# Conectores.net
KiCad netlist of a schematic drawn in EAGLE
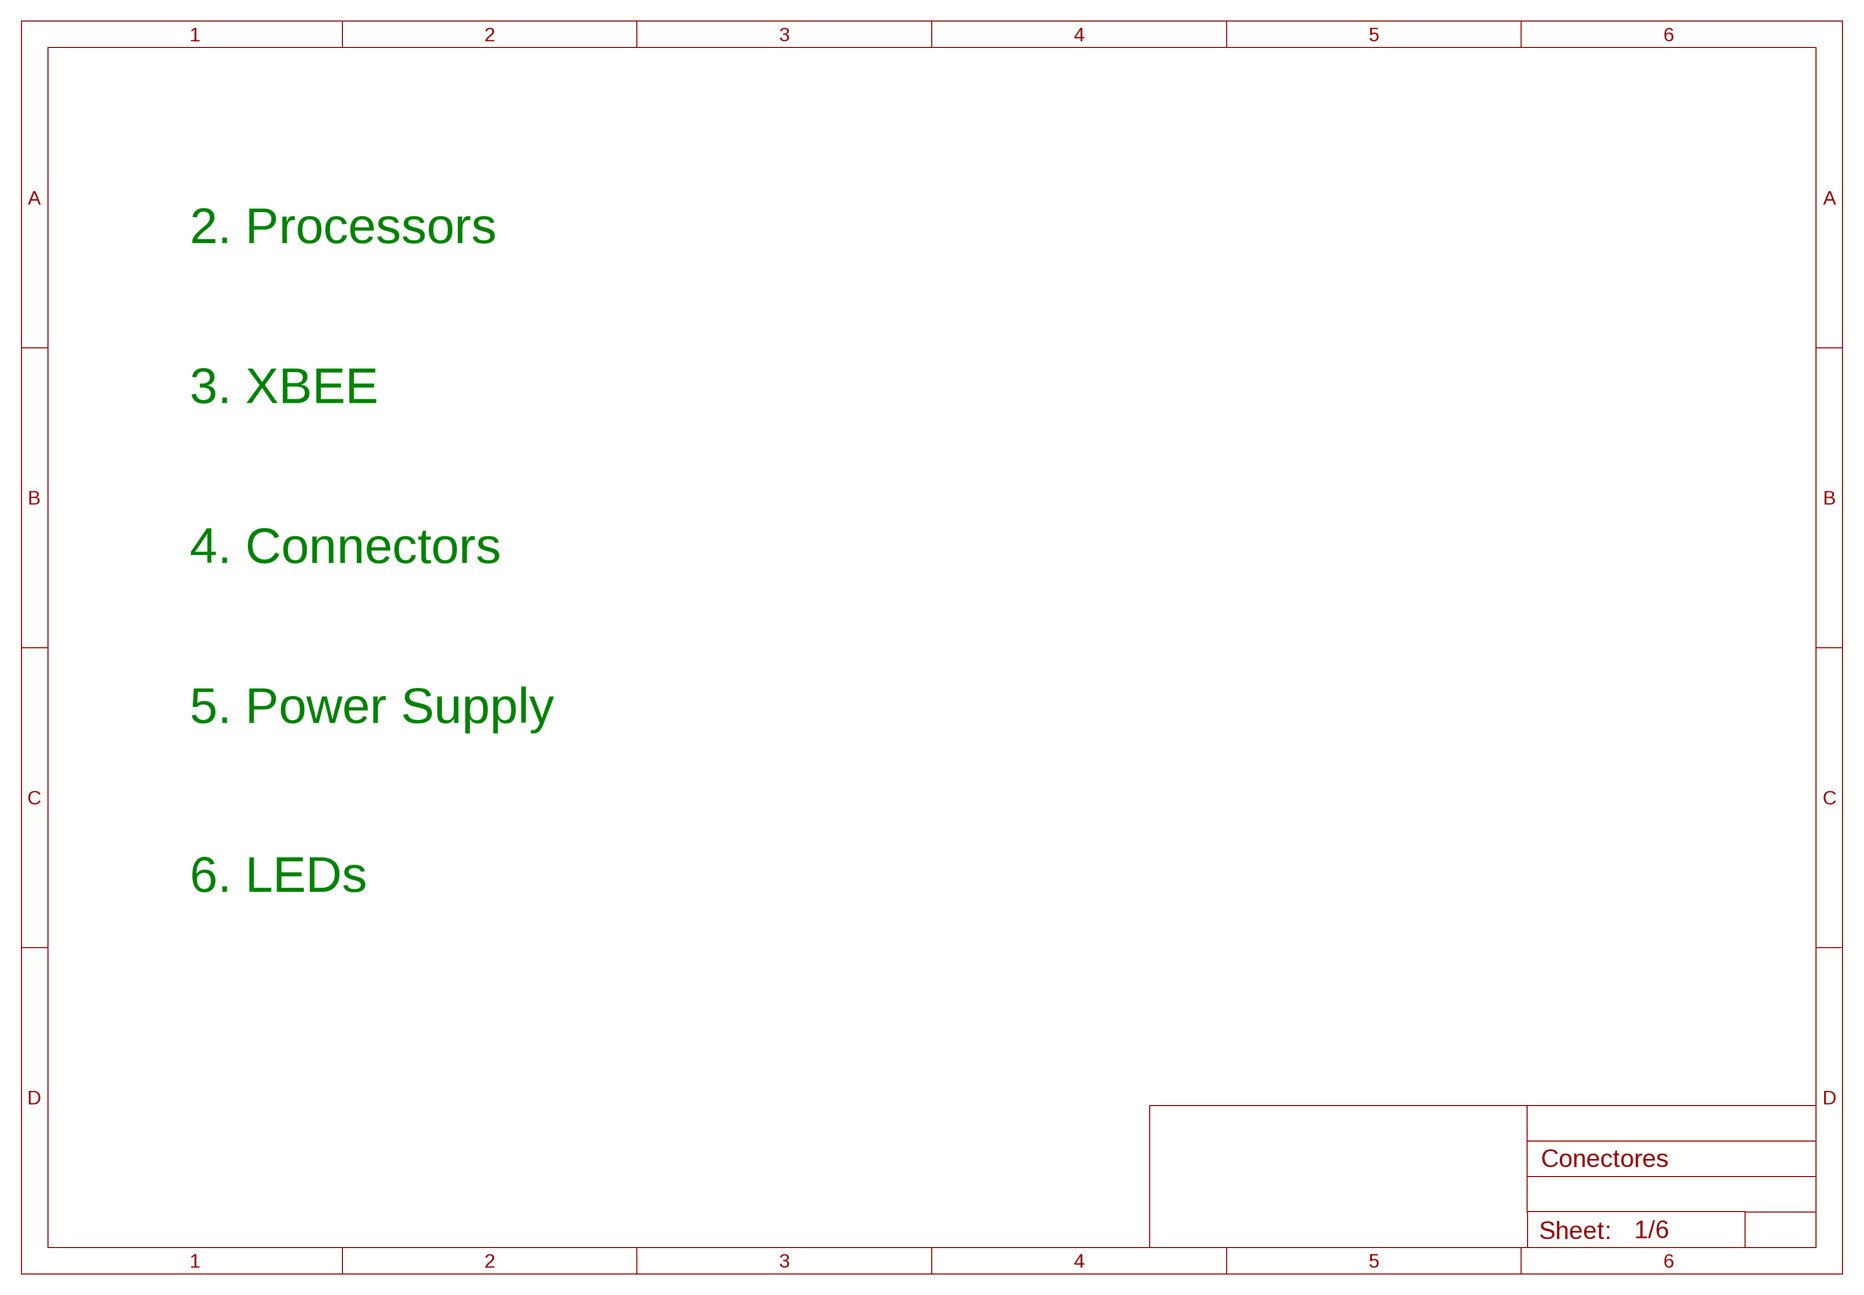
[diagram p0: schematic, sheet 1]
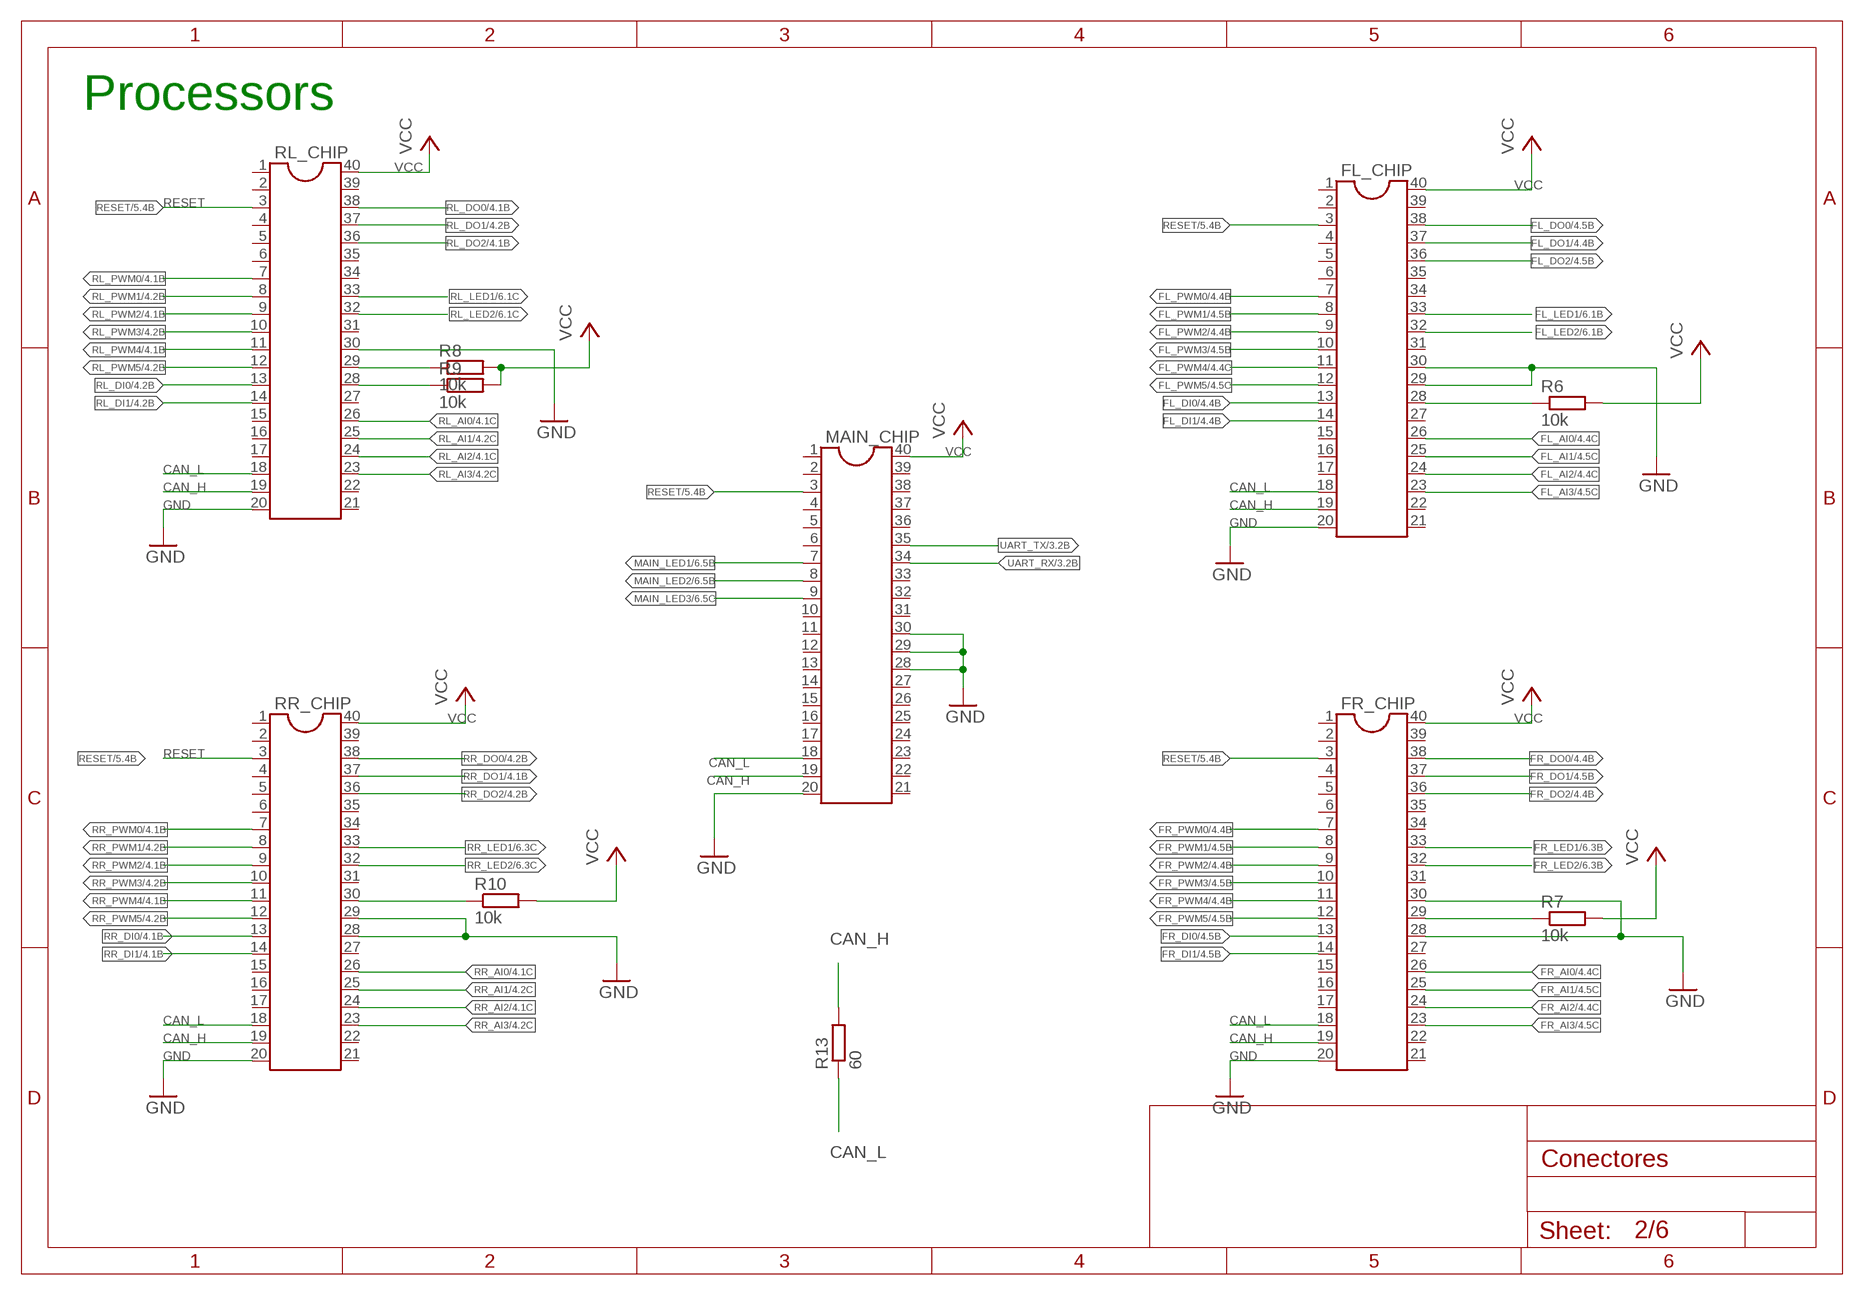
[diagram p1: schematic, sheet 2]
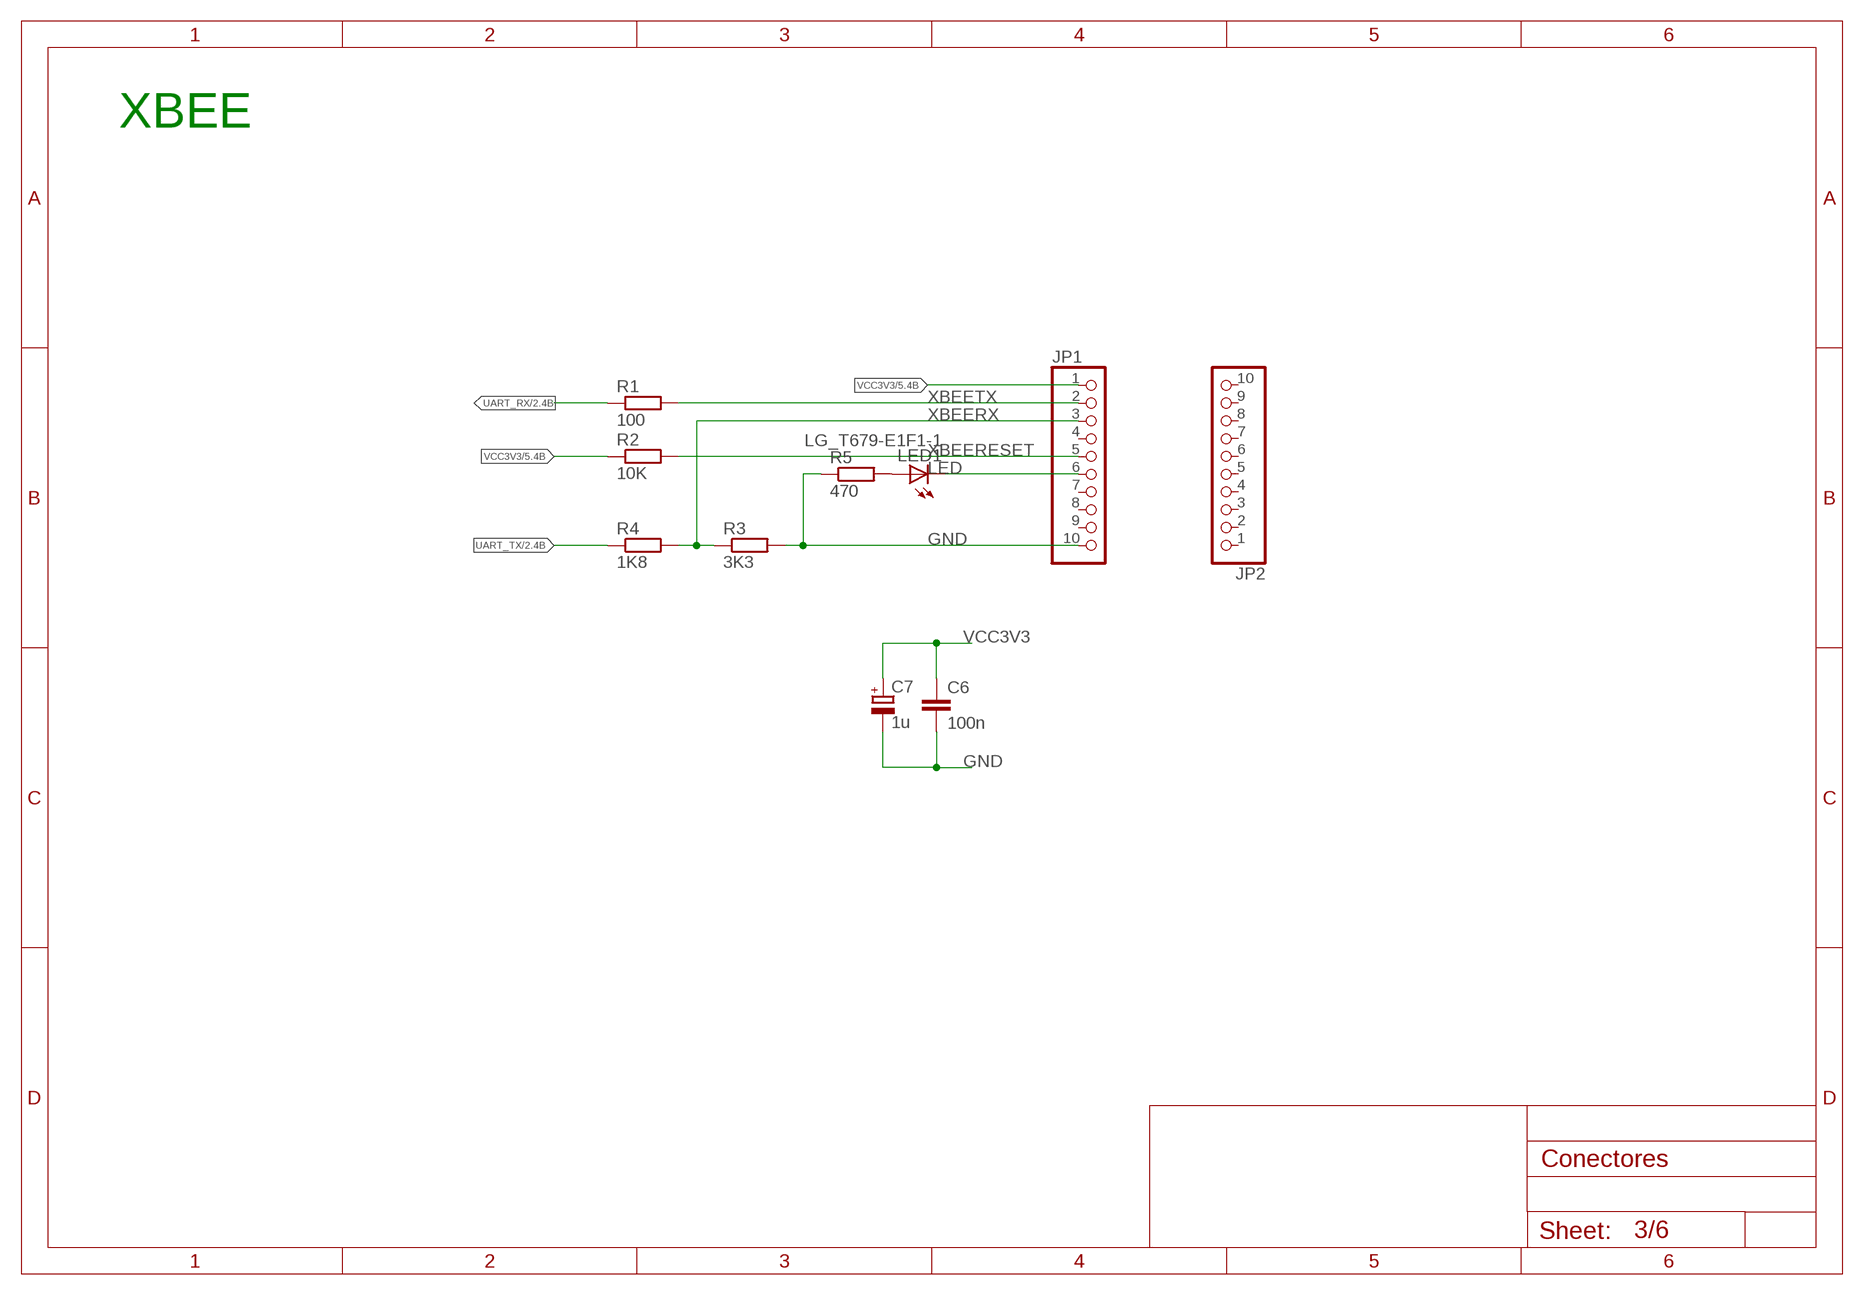
[diagram p2: schematic, sheet 3]
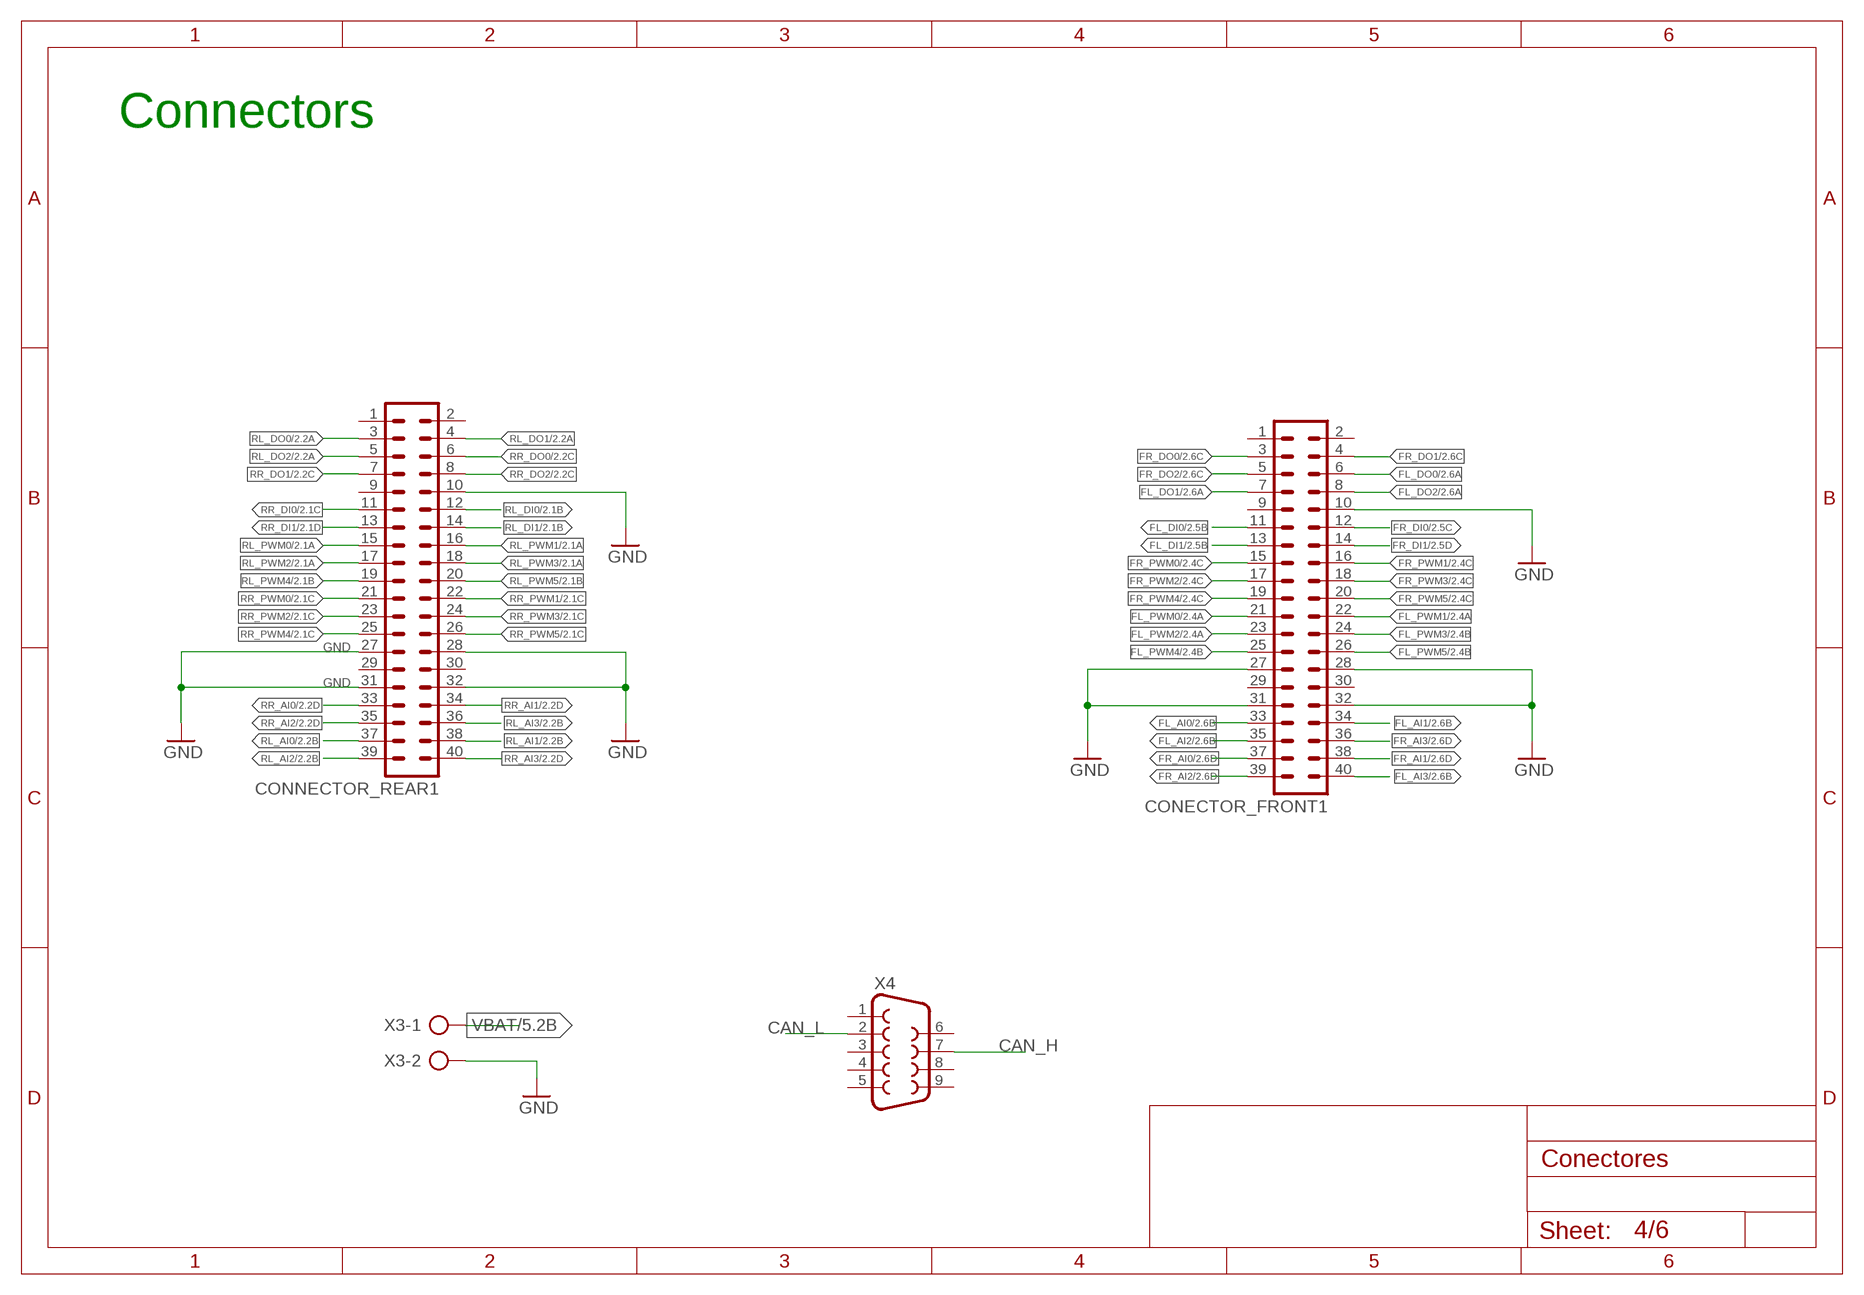
[diagram p3: schematic, sheet 4]
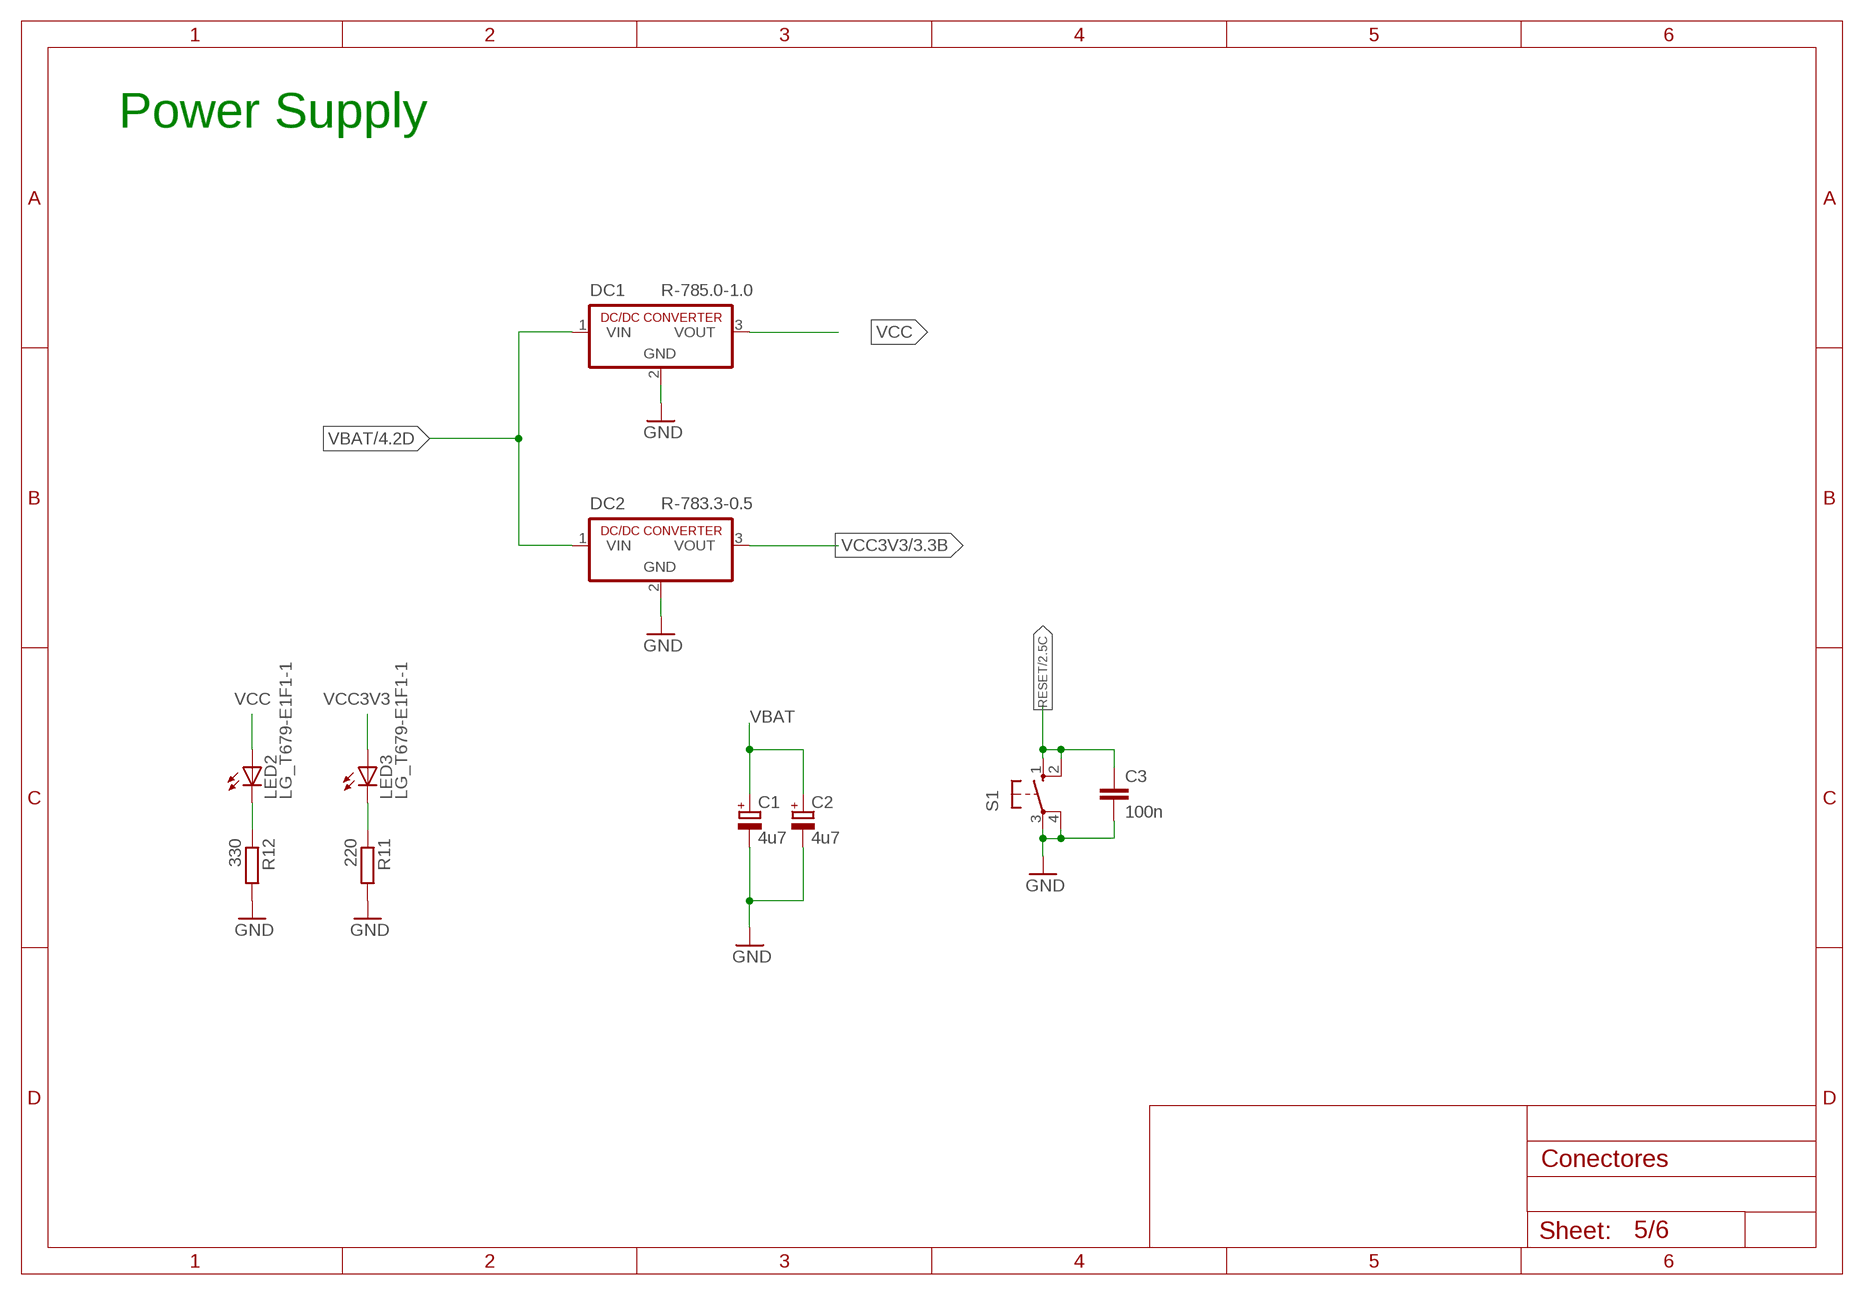
[diagram p4: schematic, sheet 5]
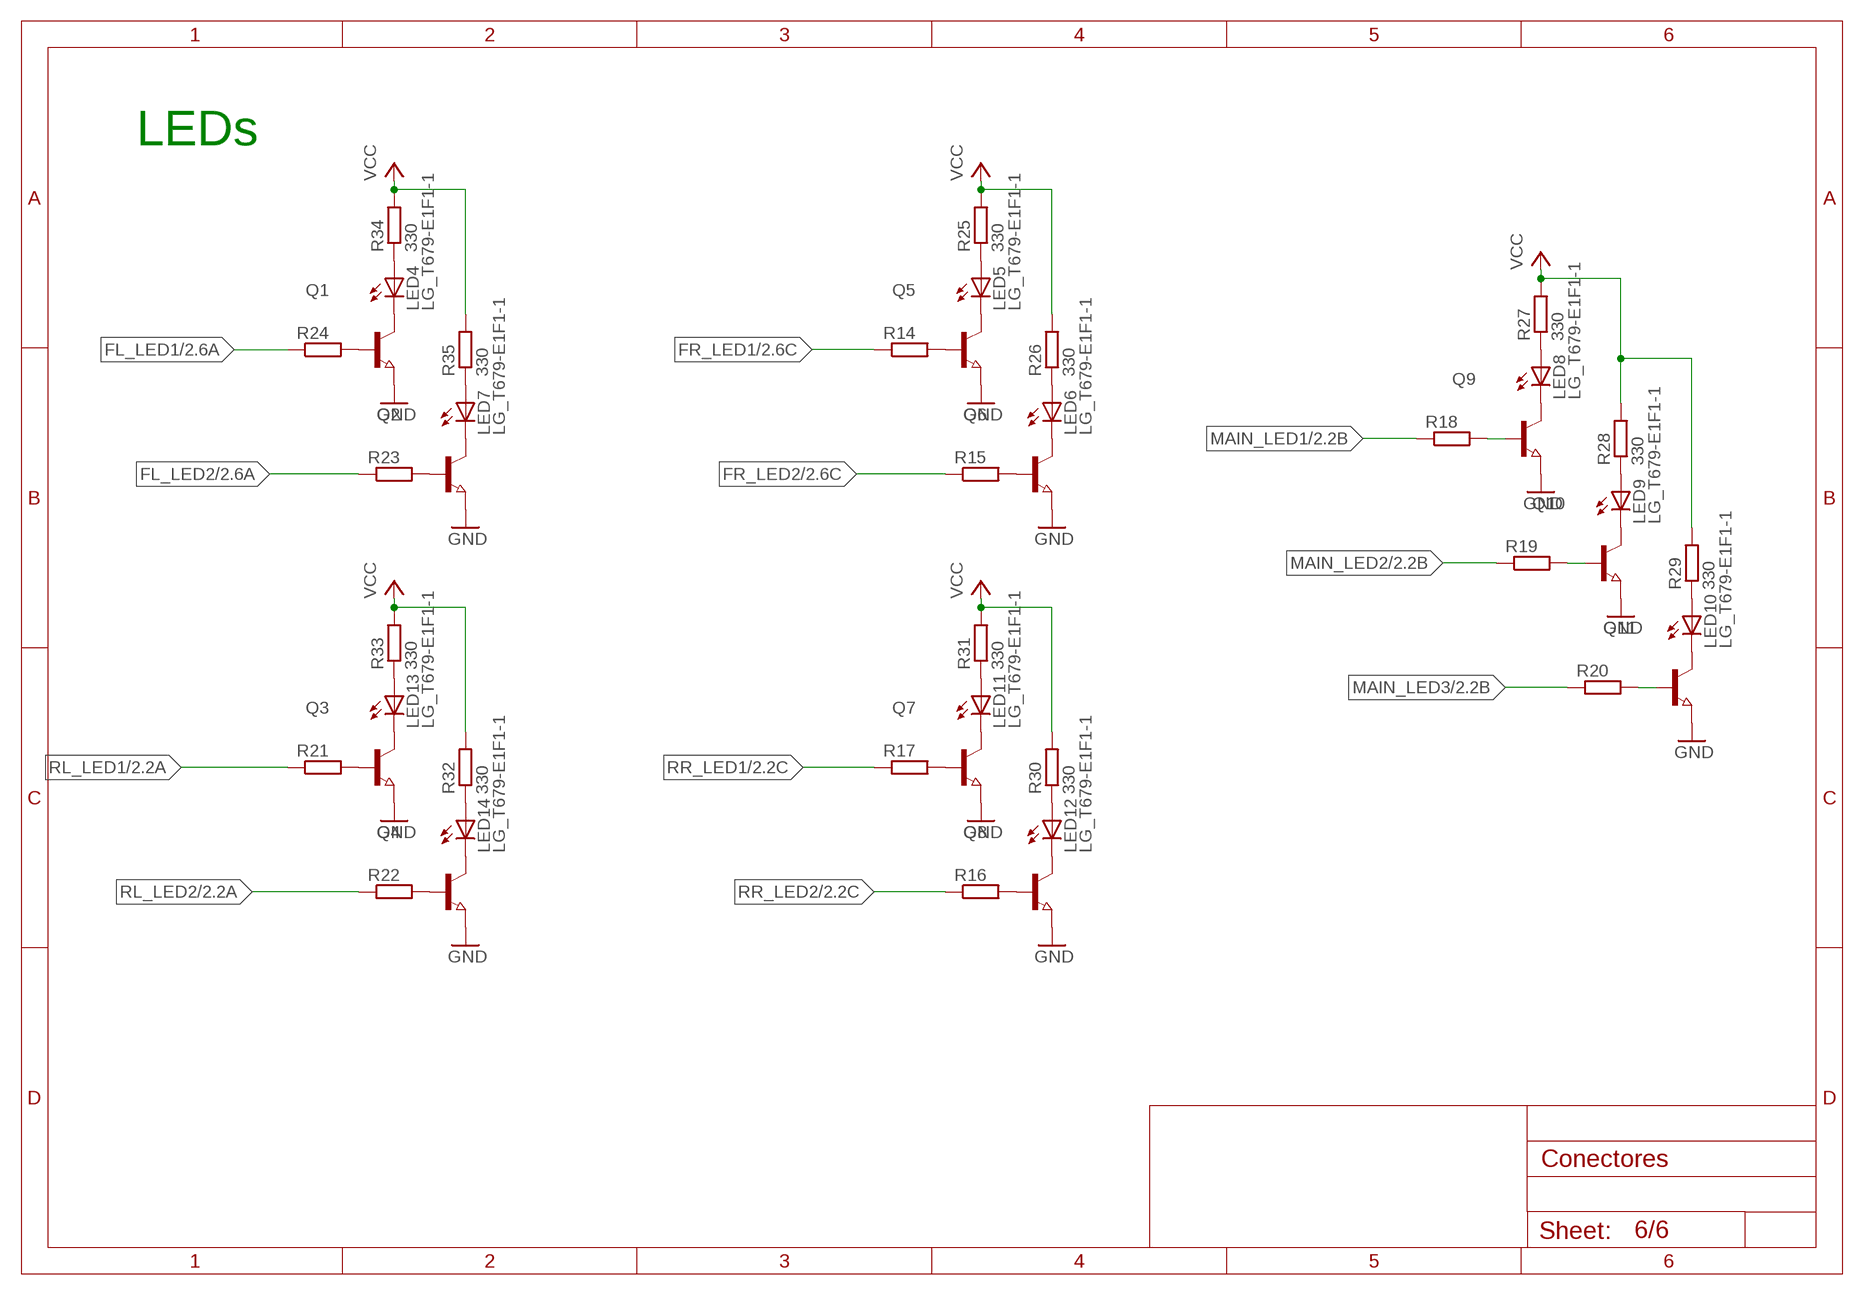
[diagram p5: schematic, sheet 6]

(export (version "E")
  (design (tool "Eeschema 10.0.6"))
  (components
    (comp (ref "C6")
      (value "100n")
      (footprint "eagle-import:C0805")
      (libsource (lib "eagle-import") (part "C-EUC0805"))
    )
    (comp (ref "C7")
      (value "1u")
      (footprint "eagle-import:CT3528")
      (libsource (lib "eagle-import") (part "CPOL-EUCT3528"))
    )
    (comp (ref "JP1")
      (value "PINHD-1X10_2.00")
      (footprint "eagle-import:1X10M")
      (libsource (lib "eagle-import") (part "PINHD-1X10_2.00"))
    )
    (comp (ref "JP2")
      (value "PINHD-1X10_2.00")
      (footprint "eagle-import:1X10M")
      (libsource (lib "eagle-import") (part "PINHD-1X10_2.00"))
    )
    (comp (ref "LED1")
      (value "LG_T679-E1F1-1")
      (footprint "eagle-import:PLCC2")
      (libsource (lib "eagle-import") (part "_T679-?-1E1F1LG"))
    )
    (comp (ref "R1")
      (value "100")
      (footprint "eagle-import:M0805")
      (libsource (lib "eagle-import") (part "resistor_R-EU_M0805"))
    )
    (comp (ref "R2")
      (value "10K")
      (footprint "eagle-import:M0805")
      (libsource (lib "eagle-import") (part "resistor_R-EU_M0805"))
    )
    (comp (ref "R3")
      (value "3K3")
      (footprint "eagle-import:M0805")
      (libsource (lib "eagle-import") (part "resistor_R-EU_M0805"))
    )
    (comp (ref "R4")
      (value "1K8")
      (footprint "eagle-import:M0805")
      (libsource (lib "eagle-import") (part "resistor_R-EU_M0805"))
    )
    (comp (ref "R5")
      (value "470")
      (footprint "eagle-import:M0805")
      (libsource (lib "eagle-import") (part "resistor_R-EU_M0805"))
    )
    (comp (ref "LED4")
      (value "LG_T679-E1F1-1")
      (footprint "eagle-import:PLCC2")
      (libsource (lib "eagle-import") (part "_T679-?-1E1F1LG"))
    )
    (comp (ref "LED5")
      (value "LG_T679-E1F1-1")
      (footprint "eagle-import:PLCC2")
      (libsource (lib "eagle-import") (part "_T679-?-1E1F1LG"))
    )
    (comp (ref "LED6")
      (value "LG_T679-E1F1-1")
      (footprint "eagle-import:PLCC2")
      (libsource (lib "eagle-import") (part "_T679-?-1E1F1LG"))
    )
    (comp (ref "LED7")
      (value "LG_T679-E1F1-1")
      (footprint "eagle-import:PLCC2")
      (libsource (lib "eagle-import") (part "_T679-?-1E1F1LG"))
    )
    (comp (ref "LED8")
      (value "LG_T679-E1F1-1")
      (footprint "eagle-import:PLCC2")
      (libsource (lib "eagle-import") (part "_T679-?-1E1F1LG"))
    )
    (comp (ref "LED9")
      (value "LG_T679-E1F1-1")
      (footprint "eagle-import:PLCC2")
      (libsource (lib "eagle-import") (part "_T679-?-1E1F1LG"))
    )
    (comp (ref "LED10")
      (value "LG_T679-E1F1-1")
      (footprint "eagle-import:PLCC2")
      (libsource (lib "eagle-import") (part "_T679-?-1E1F1LG"))
    )
    (comp (ref "LED11")
      (value "LG_T679-E1F1-1")
      (footprint "eagle-import:PLCC2")
      (libsource (lib "eagle-import") (part "_T679-?-1E1F1LG"))
    )
    (comp (ref "LED12")
      (value "LG_T679-E1F1-1")
      (footprint "eagle-import:PLCC2")
      (libsource (lib "eagle-import") (part "_T679-?-1E1F1LG"))
    )
    (comp (ref "LED13")
      (value "LG_T679-E1F1-1")
      (footprint "eagle-import:PLCC2")
      (libsource (lib "eagle-import") (part "_T679-?-1E1F1LG"))
    )
    (comp (ref "LED14")
      (value "LG_T679-E1F1-1")
      (footprint "eagle-import:PLCC2")
      (libsource (lib "eagle-import") (part "_T679-?-1E1F1LG"))
    )
    (comp (ref "Q1")
      (value "NPN-TRANSISTOR_SOT23")
      (footprint "eagle-import:SOT23")
      (libsource (lib "eagle-import") (part "NPN-TRANSISTOR_SOT23"))
    )
    (comp (ref "Q2")
      (value "NPN-TRANSISTOR_SOT23")
      (footprint "eagle-import:SOT23")
      (libsource (lib "eagle-import") (part "NPN-TRANSISTOR_SOT23"))
    )
    (comp (ref "Q3")
      (value "NPN-TRANSISTOR_SOT23")
      (footprint "eagle-import:SOT23")
      (libsource (lib "eagle-import") (part "NPN-TRANSISTOR_SOT23"))
    )
    (comp (ref "Q4")
      (value "NPN-TRANSISTOR_SOT23")
      (footprint "eagle-import:SOT23")
      (libsource (lib "eagle-import") (part "NPN-TRANSISTOR_SOT23"))
    )
    (comp (ref "Q5")
      (value "NPN-TRANSISTOR_SOT23")
      (footprint "eagle-import:SOT23")
      (libsource (lib "eagle-import") (part "NPN-TRANSISTOR_SOT23"))
    )
    (comp (ref "Q6")
      (value "NPN-TRANSISTOR_SOT23")
      (footprint "eagle-import:SOT23")
      (libsource (lib "eagle-import") (part "NPN-TRANSISTOR_SOT23"))
    )
    (comp (ref "Q7")
      (value "NPN-TRANSISTOR_SOT23")
      (footprint "eagle-import:SOT23")
      (libsource (lib "eagle-import") (part "NPN-TRANSISTOR_SOT23"))
    )
    (comp (ref "Q8")
      (value "NPN-TRANSISTOR_SOT23")
      (footprint "eagle-import:SOT23")
      (libsource (lib "eagle-import") (part "NPN-TRANSISTOR_SOT23"))
    )
    (comp (ref "Q9")
      (value "NPN-TRANSISTOR_SOT23")
      (footprint "eagle-import:SOT23")
      (libsource (lib "eagle-import") (part "NPN-TRANSISTOR_SOT23"))
    )
    (comp (ref "Q10")
      (value "NPN-TRANSISTOR_SOT23")
      (footprint "eagle-import:SOT23")
      (libsource (lib "eagle-import") (part "NPN-TRANSISTOR_SOT23"))
    )
    (comp (ref "Q11")
      (value "NPN-TRANSISTOR_SOT23")
      (footprint "eagle-import:SOT23")
      (libsource (lib "eagle-import") (part "NPN-TRANSISTOR_SOT23"))
    )
    (comp (ref "R14")
      (value "R-EU_R0805")
      (footprint "eagle-import:R0805")
      (libsource (lib "eagle-import") (part "R-EU_R0805"))
    )
    (comp (ref "R15")
      (value "R-EU_R0805")
      (footprint "eagle-import:R0805")
      (libsource (lib "eagle-import") (part "R-EU_R0805"))
    )
    (comp (ref "R16")
      (value "R-EU_R0805")
      (footprint "eagle-import:R0805")
      (libsource (lib "eagle-import") (part "R-EU_R0805"))
    )
    (comp (ref "R17")
      (value "R-EU_R0805")
      (footprint "eagle-import:R0805")
      (libsource (lib "eagle-import") (part "R-EU_R0805"))
    )
    (comp (ref "R18")
      (value "R-EU_R0805")
      (footprint "eagle-import:R0805")
      (libsource (lib "eagle-import") (part "R-EU_R0805"))
    )
    (comp (ref "R19")
      (value "R-EU_R0805")
      (footprint "eagle-import:R0805")
      (libsource (lib "eagle-import") (part "R-EU_R0805"))
    )
    (comp (ref "R20")
      (value "R-EU_R0805")
      (footprint "eagle-import:R0805")
      (libsource (lib "eagle-import") (part "R-EU_R0805"))
    )
    (comp (ref "R21")
      (value "R-EU_R0805")
      (footprint "eagle-import:R0805")
      (libsource (lib "eagle-import") (part "R-EU_R0805"))
    )
    (comp (ref "R22")
      (value "R-EU_R0805")
      (footprint "eagle-import:R0805")
      (libsource (lib "eagle-import") (part "R-EU_R0805"))
    )
    (comp (ref "R23")
      (value "R-EU_R0805")
      (footprint "eagle-import:R0805")
      (libsource (lib "eagle-import") (part "R-EU_R0805"))
    )
    (comp (ref "R24")
      (value "R-EU_R0805")
      (footprint "eagle-import:R0805")
      (libsource (lib "eagle-import") (part "R-EU_R0805"))
    )
    (comp (ref "R25")
      (value "330")
      (footprint "eagle-import:R0805")
      (libsource (lib "eagle-import") (part "R-EU_R0805"))
    )
    (comp (ref "R26")
      (value "330")
      (footprint "eagle-import:R0805")
      (libsource (lib "eagle-import") (part "R-EU_R0805"))
    )
    (comp (ref "R27")
      (value "330")
      (footprint "eagle-import:R0805")
      (libsource (lib "eagle-import") (part "R-EU_R0805"))
    )
    (comp (ref "R28")
      (value "330")
      (footprint "eagle-import:R0805")
      (libsource (lib "eagle-import") (part "R-EU_R0805"))
    )
    (comp (ref "R29")
      (value "330")
      (footprint "eagle-import:R0805")
      (libsource (lib "eagle-import") (part "R-EU_R0805"))
    )
    (comp (ref "R30")
      (value "330")
      (footprint "eagle-import:R0805")
      (libsource (lib "eagle-import") (part "R-EU_R0805"))
    )
    (comp (ref "R31")
      (value "330")
      (footprint "eagle-import:R0805")
      (libsource (lib "eagle-import") (part "R-EU_R0805"))
    )
    (comp (ref "R32")
      (value "330")
      (footprint "eagle-import:R0805")
      (libsource (lib "eagle-import") (part "R-EU_R0805"))
    )
    (comp (ref "R33")
      (value "330")
      (footprint "eagle-import:R0805")
      (libsource (lib "eagle-import") (part "R-EU_R0805"))
    )
    (comp (ref "R34")
      (value "330")
      (footprint "eagle-import:R0805")
      (libsource (lib "eagle-import") (part "R-EU_R0805"))
    )
    (comp (ref "R35")
      (value "330")
      (footprint "eagle-import:R0805")
      (libsource (lib "eagle-import") (part "R-EU_R0805"))
    )
    (comp (ref "CONECTOR_FRONT1")
      (value "ML40")
      (footprint "eagle-import:ML40")
      (libsource (lib "eagle-import") (part "ML40"))
    )
    (comp (ref "CONNECTOR_REAR1")
      (value "ML40")
      (footprint "eagle-import:ML40")
      (libsource (lib "eagle-import") (part "ML40"))
    )
    (comp (ref "X3")
      (value "AK300/2")
      (footprint "eagle-import:AK300_2")
      (libsource (lib "eagle-import") (part "AK300/2"))
    )
    (comp (ref "X4")
      (value "F09HP")
      (footprint "eagle-import:F09HP")
      (libsource (lib "eagle-import") (part "F09HP"))
    )
    (comp (ref "FL_CHIP")
      (value "DIL40")
      (footprint "eagle-import:DIL40")
      (libsource (lib "eagle-import") (part "DIL40"))
    )
    (comp (ref "FR_CHIP")
      (value "DIL40")
      (footprint "eagle-import:DIL40")
      (libsource (lib "eagle-import") (part "DIL40"))
    )
    (comp (ref "MAIN_CHIP")
      (value "DIL40")
      (footprint "eagle-import:DIL40")
      (libsource (lib "eagle-import") (part "DIL40"))
    )
    (comp (ref "R6")
      (value "10k")
      (footprint "eagle-import:M0805")
      (libsource (lib "eagle-import") (part "R-EU_M0805"))
    )
    (comp (ref "R7")
      (value "10k")
      (footprint "eagle-import:M0805")
      (libsource (lib "eagle-import") (part "R-EU_M0805"))
    )
    (comp (ref "R8")
      (value "10k")
      (footprint "eagle-import:M0805")
      (libsource (lib "eagle-import") (part "R-EU_M0805"))
    )
    (comp (ref "R9")
      (value "10k")
      (footprint "eagle-import:M0805")
      (libsource (lib "eagle-import") (part "R-EU_M0805"))
    )
    (comp (ref "R10")
      (value "10k")
      (footprint "eagle-import:M0805")
      (libsource (lib "eagle-import") (part "R-EU_M0805"))
    )
    (comp (ref "R13")
      (value "60")
      (footprint "eagle-import:R0805")
      (libsource (lib "eagle-import") (part "R-EU_R0805"))
    )
    (comp (ref "RL_CHIP")
      (value "DIL40")
      (footprint "eagle-import:DIL40")
      (libsource (lib "eagle-import") (part "DIL40"))
    )
    (comp (ref "RR_CHIP")
      (value "DIL40")
      (footprint "eagle-import:DIL40")
      (libsource (lib "eagle-import") (part "DIL40"))
    )
    (comp (ref "C1")
      (value "4u7")
      (footprint "eagle-import:SMC_E")
      (libsource (lib "eagle-import") (part "CPOL-EUSMCE"))
    )
    (comp (ref "C2")
      (value "4u7")
      (footprint "eagle-import:SMC_E")
      (libsource (lib "eagle-import") (part "CPOL-EUSMCE"))
    )
    (comp (ref "C3")
      (value "100n")
      (footprint "eagle-import:C0805K")
      (libsource (lib "eagle-import") (part "C-EUC0805K"))
    )
    (comp (ref "DC1")
      (value "R-785.0-1.0")
      (footprint "eagle-import:SIP3")
      (libsource (lib "eagle-import") (part "R-78C-1.05.0"))
    )
    (comp (ref "DC2")
      (value "R-783.3-0.5")
      (footprint "eagle-import:SIP3")
      (libsource (lib "eagle-import") (part "R-78C-1.05.0"))
    )
    (comp (ref "LED2")
      (value "LG_T679-E1F1-1")
      (footprint "eagle-import:PLCC2")
      (libsource (lib "eagle-import") (part "_T679-?-1E1F1LG"))
    )
    (comp (ref "LED3")
      (value "LG_T679-E1F1-1")
      (footprint "eagle-import:PLCC2")
      (libsource (lib "eagle-import") (part "_T679-?-1E1F1LG"))
    )
    (comp (ref "R11")
      (value "220")
      (footprint "eagle-import:R0805")
      (libsource (lib "eagle-import") (part "R-EU_R0805"))
    )
    (comp (ref "R12")
      (value "330")
      (footprint "eagle-import:R0805")
      (libsource (lib "eagle-import") (part "R-EU_R0805"))
    )
    (comp (ref "S1")
      (value "10-XX")
      (footprint "eagle-import:B3F-10XX")
      (fields (field (name "MPN") "B3F-1000"))
      (libsource (lib "eagle-import") (part "10-XX"))
    )
  )
  (nets
    (net (code "1") (name "CAN_H") (class "Default")
      (node (ref "FL_CHIP") (pin "19") (pinfunction "19_19") (pintype "passive"))
      (node (ref "FR_CHIP") (pin "19") (pinfunction "19_19") (pintype "passive"))
      (node (ref "MAIN_CHIP") (pin "19") (pinfunction "19_19") (pintype "passive"))
      (node (ref "R13") (pin "2") (pinfunction "2_2") (pintype "passive"))
      (node (ref "RL_CHIP") (pin "19") (pinfunction "19_19") (pintype "passive"))
      (node (ref "RR_CHIP") (pin "19") (pinfunction "19_19") (pintype "passive"))
      (node (ref "X4") (pin "7") (pinfunction "7_7") (pintype "passive"))
    )
    (net (code "2") (name "CAN_L") (class "Default")
      (node (ref "FL_CHIP") (pin "18") (pinfunction "18_18") (pintype "passive"))
      (node (ref "FR_CHIP") (pin "18") (pinfunction "18_18") (pintype "passive"))
      (node (ref "MAIN_CHIP") (pin "18") (pinfunction "18_18") (pintype "passive"))
      (node (ref "R13") (pin "1") (pinfunction "1_1") (pintype "passive"))
      (node (ref "RL_CHIP") (pin "18") (pinfunction "18_18") (pintype "passive"))
      (node (ref "RR_CHIP") (pin "18") (pinfunction "18_18") (pintype "passive"))
      (node (ref "X4") (pin "2") (pinfunction "2_2") (pintype "passive"))
    )
    (net (code "3") (name "FL_AI0") (class "Default")
      (node (ref "CONECTOR_FRONT1") (pin "33") (pinfunction "33_33") (pintype "passive"))
      (node (ref "FL_CHIP") (pin "26") (pinfunction "26_26") (pintype "passive"))
    )
    (net (code "4") (name "FL_AI1") (class "Default")
      (node (ref "CONECTOR_FRONT1") (pin "34") (pinfunction "34_34") (pintype "passive"))
      (node (ref "FL_CHIP") (pin "25") (pinfunction "25_25") (pintype "passive"))
    )
    (net (code "5") (name "FL_AI2") (class "Default")
      (node (ref "CONECTOR_FRONT1") (pin "35") (pinfunction "35_35") (pintype "passive"))
      (node (ref "FL_CHIP") (pin "24") (pinfunction "24_24") (pintype "passive"))
    )
    (net (code "6") (name "FL_AI3") (class "Default")
      (node (ref "CONECTOR_FRONT1") (pin "40") (pinfunction "40_40") (pintype "passive"))
      (node (ref "FL_CHIP") (pin "23") (pinfunction "23_23") (pintype "passive"))
    )
    (net (code "7") (name "FL_DI0") (class "Default")
      (node (ref "CONECTOR_FRONT1") (pin "11") (pinfunction "11_11") (pintype "passive"))
      (node (ref "FL_CHIP") (pin "13") (pinfunction "13_13") (pintype "passive"))
    )
    (net (code "8") (name "FL_DI1") (class "Default")
      (node (ref "CONECTOR_FRONT1") (pin "13") (pinfunction "13_13") (pintype "passive"))
      (node (ref "FL_CHIP") (pin "14") (pinfunction "14_14") (pintype "passive"))
    )
    (net (code "9") (name "FL_DO0") (class "Default")
      (node (ref "CONECTOR_FRONT1") (pin "6") (pinfunction "6_6") (pintype "passive"))
      (node (ref "FL_CHIP") (pin "38") (pinfunction "38_38") (pintype "passive"))
    )
    (net (code "10") (name "FL_DO1") (class "Default")
      (node (ref "CONECTOR_FRONT1") (pin "7") (pinfunction "7_7") (pintype "passive"))
      (node (ref "FL_CHIP") (pin "37") (pinfunction "37_37") (pintype "passive"))
    )
    (net (code "11") (name "FL_DO2") (class "Default")
      (node (ref "CONECTOR_FRONT1") (pin "8") (pinfunction "8_8") (pintype "passive"))
      (node (ref "FL_CHIP") (pin "36") (pinfunction "36_36") (pintype "passive"))
    )
    (net (code "12") (name "FL_LED1") (class "Default")
      (node (ref "FL_CHIP") (pin "33") (pinfunction "33_33") (pintype "passive"))
      (node (ref "R24") (pin "1") (pinfunction "1_1") (pintype "passive"))
    )
    (net (code "13") (name "FL_LED2") (class "Default")
      (node (ref "FL_CHIP") (pin "32") (pinfunction "32_32") (pintype "passive"))
      (node (ref "R23") (pin "1") (pinfunction "1_1") (pintype "passive"))
    )
    (net (code "14") (name "FL_PWM0") (class "Default")
      (node (ref "CONECTOR_FRONT1") (pin "21") (pinfunction "21_21") (pintype "passive"))
      (node (ref "FL_CHIP") (pin "7") (pinfunction "7_7") (pintype "passive"))
    )
    (net (code "15") (name "FL_PWM1") (class "Default")
      (node (ref "CONECTOR_FRONT1") (pin "22") (pinfunction "22_22") (pintype "passive"))
      (node (ref "FL_CHIP") (pin "8") (pinfunction "8_8") (pintype "passive"))
    )
    (net (code "16") (name "FL_PWM2") (class "Default")
      (node (ref "CONECTOR_FRONT1") (pin "23") (pinfunction "23_23") (pintype "passive"))
      (node (ref "FL_CHIP") (pin "9") (pinfunction "9_9") (pintype "passive"))
    )
    (net (code "17") (name "FL_PWM3") (class "Default")
      (node (ref "CONECTOR_FRONT1") (pin "24") (pinfunction "24_24") (pintype "passive"))
      (node (ref "FL_CHIP") (pin "10") (pinfunction "10_10") (pintype "passive"))
    )
    (net (code "18") (name "FL_PWM4") (class "Default")
      (node (ref "CONECTOR_FRONT1") (pin "25") (pinfunction "25_25") (pintype "passive"))
      (node (ref "FL_CHIP") (pin "11") (pinfunction "11_11") (pintype "passive"))
    )
    (net (code "19") (name "FL_PWM5") (class "Default")
      (node (ref "CONECTOR_FRONT1") (pin "26") (pinfunction "26_26") (pintype "passive"))
      (node (ref "FL_CHIP") (pin "12") (pinfunction "12_12") (pintype "passive"))
    )
    (net (code "20") (name "FR_AI0") (class "Default")
      (node (ref "CONECTOR_FRONT1") (pin "37") (pinfunction "37_37") (pintype "passive"))
      (node (ref "FR_CHIP") (pin "26") (pinfunction "26_26") (pintype "passive"))
    )
    (net (code "21") (name "FR_AI1") (class "Default")
      (node (ref "CONECTOR_FRONT1") (pin "38") (pinfunction "38_38") (pintype "passive"))
      (node (ref "FR_CHIP") (pin "25") (pinfunction "25_25") (pintype "passive"))
    )
    (net (code "22") (name "FR_AI2") (class "Default")
      (node (ref "CONECTOR_FRONT1") (pin "39") (pinfunction "39_39") (pintype "passive"))
      (node (ref "FR_CHIP") (pin "24") (pinfunction "24_24") (pintype "passive"))
    )
    (net (code "23") (name "FR_AI3") (class "Default")
      (node (ref "CONECTOR_FRONT1") (pin "36") (pinfunction "36_36") (pintype "passive"))
      (node (ref "FR_CHIP") (pin "23") (pinfunction "23_23") (pintype "passive"))
    )
    (net (code "24") (name "FR_DI0") (class "Default")
      (node (ref "CONECTOR_FRONT1") (pin "12") (pinfunction "12_12") (pintype "passive"))
      (node (ref "FR_CHIP") (pin "13") (pinfunction "13_13") (pintype "passive"))
    )
    (net (code "25") (name "FR_DI1") (class "Default")
      (node (ref "CONECTOR_FRONT1") (pin "14") (pinfunction "14_14") (pintype "passive"))
      (node (ref "FR_CHIP") (pin "14") (pinfunction "14_14") (pintype "passive"))
    )
    (net (code "26") (name "FR_DO0") (class "Default")
      (node (ref "CONECTOR_FRONT1") (pin "3") (pinfunction "3_3") (pintype "passive"))
      (node (ref "FR_CHIP") (pin "38") (pinfunction "38_38") (pintype "passive"))
    )
    (net (code "27") (name "FR_DO1") (class "Default")
      (node (ref "CONECTOR_FRONT1") (pin "4") (pinfunction "4_4") (pintype "passive"))
      (node (ref "FR_CHIP") (pin "37") (pinfunction "37_37") (pintype "passive"))
    )
    (net (code "28") (name "FR_DO2") (class "Default")
      (node (ref "CONECTOR_FRONT1") (pin "5") (pinfunction "5_5") (pintype "passive"))
      (node (ref "FR_CHIP") (pin "36") (pinfunction "36_36") (pintype "passive"))
    )
    (net (code "29") (name "FR_LED1") (class "Default")
      (node (ref "FR_CHIP") (pin "33") (pinfunction "33_33") (pintype "passive"))
      (node (ref "R14") (pin "1") (pinfunction "1_1") (pintype "passive"))
    )
    (net (code "30") (name "FR_LED2") (class "Default")
      (node (ref "FR_CHIP") (pin "32") (pinfunction "32_32") (pintype "passive"))
      (node (ref "R15") (pin "1") (pinfunction "1_1") (pintype "passive"))
    )
    (net (code "31") (name "FR_PWM0") (class "Default")
      (node (ref "CONECTOR_FRONT1") (pin "15") (pinfunction "15_15") (pintype "passive"))
      (node (ref "FR_CHIP") (pin "7") (pinfunction "7_7") (pintype "passive"))
    )
    (net (code "32") (name "FR_PWM1") (class "Default")
      (node (ref "CONECTOR_FRONT1") (pin "16") (pinfunction "16_16") (pintype "passive"))
      (node (ref "FR_CHIP") (pin "8") (pinfunction "8_8") (pintype "passive"))
    )
    (net (code "33") (name "FR_PWM2") (class "Default")
      (node (ref "CONECTOR_FRONT1") (pin "17") (pinfunction "17_17") (pintype "passive"))
      (node (ref "FR_CHIP") (pin "9") (pinfunction "9_9") (pintype "passive"))
    )
    (net (code "34") (name "FR_PWM3") (class "Default")
      (node (ref "CONECTOR_FRONT1") (pin "18") (pinfunction "18_18") (pintype "passive"))
      (node (ref "FR_CHIP") (pin "10") (pinfunction "10_10") (pintype "passive"))
    )
    (net (code "35") (name "FR_PWM4") (class "Default")
      (node (ref "CONECTOR_FRONT1") (pin "19") (pinfunction "19_19") (pintype "passive"))
      (node (ref "FR_CHIP") (pin "11") (pinfunction "11_11") (pintype "passive"))
    )
    (net (code "36") (name "FR_PWM5") (class "Default")
      (node (ref "CONECTOR_FRONT1") (pin "20") (pinfunction "20_20") (pintype "passive"))
      (node (ref "FR_CHIP") (pin "12") (pinfunction "12_12") (pintype "passive"))
    )
    (net (code "37") (name "GND") (class "Default")
      (node (ref "C1") (pin "-") (pinfunction "-_-") (pintype "passive"))
      (node (ref "C2") (pin "-") (pinfunction "-_-") (pintype "passive"))
      (node (ref "C3") (pin "2") (pinfunction "2_2") (pintype "passive"))
      (node (ref "C6") (pin "2") (pinfunction "2_2") (pintype "passive"))
      (node (ref "C7") (pin "-") (pinfunction "-_-") (pintype "passive"))
      (node (ref "CONECTOR_FRONT1") (pin "10") (pinfunction "10_10") (pintype "passive"))
      (node (ref "CONECTOR_FRONT1") (pin "27") (pinfunction "27_27") (pintype "passive"))
      (node (ref "CONECTOR_FRONT1") (pin "28") (pinfunction "28_28") (pintype "passive"))
      (node (ref "CONECTOR_FRONT1") (pin "31") (pinfunction "31_31") (pintype "passive"))
      (node (ref "CONECTOR_FRONT1") (pin "32") (pinfunction "32_32") (pintype "passive"))
      (node (ref "CONNECTOR_REAR1") (pin "10") (pinfunction "10_10") (pintype "passive"))
      (node (ref "CONNECTOR_REAR1") (pin "27") (pinfunction "27_27") (pintype "passive"))
      (node (ref "CONNECTOR_REAR1") (pin "28") (pinfunction "28_28") (pintype "passive"))
      (node (ref "CONNECTOR_REAR1") (pin "31") (pinfunction "31_31") (pintype "passive"))
      (node (ref "CONNECTOR_REAR1") (pin "32") (pinfunction "32_32") (pintype "passive"))
      (node (ref "DC1") (pin "2") (pinfunction "GND_2") (pintype "passive"))
      (node (ref "DC2") (pin "2") (pinfunction "GND_2") (pintype "passive"))
      (node (ref "FL_CHIP") (pin "20") (pinfunction "20_20") (pintype "passive"))
      (node (ref "FL_CHIP") (pin "29") (pinfunction "29_29") (pintype "passive"))
      (node (ref "FL_CHIP") (pin "30") (pinfunction "30_30") (pintype "passive"))
      (node (ref "FR_CHIP") (pin "20") (pinfunction "20_20") (pintype "passive"))
      (node (ref "FR_CHIP") (pin "28") (pinfunction "28_28") (pintype "passive"))
      (node (ref "FR_CHIP") (pin "30") (pinfunction "30_30") (pintype "passive"))
      (node (ref "JP1") (pin "10") (pinfunction "10_10") (pintype "passive"))
      (node (ref "MAIN_CHIP") (pin "20") (pinfunction "20_20") (pintype "passive"))
      (node (ref "MAIN_CHIP") (pin "28") (pinfunction "28_28") (pintype "passive"))
      (node (ref "MAIN_CHIP") (pin "29") (pinfunction "29_29") (pintype "passive"))
      (node (ref "MAIN_CHIP") (pin "30") (pinfunction "30_30") (pintype "passive"))
      (node (ref "Q1") (pin "2") (pinfunction "E_2") (pintype "passive"))
      (node (ref "Q10") (pin "2") (pinfunction "E_2") (pintype "passive"))
      (node (ref "Q11") (pin "2") (pinfunction "E_2") (pintype "passive"))
      (node (ref "Q2") (pin "2") (pinfunction "E_2") (pintype "passive"))
      (node (ref "Q3") (pin "2") (pinfunction "E_2") (pintype "passive"))
      (node (ref "Q4") (pin "2") (pinfunction "E_2") (pintype "passive"))
      (node (ref "Q5") (pin "2") (pinfunction "E_2") (pintype "passive"))
      (node (ref "Q6") (pin "2") (pinfunction "E_2") (pintype "passive"))
      (node (ref "Q7") (pin "2") (pinfunction "E_2") (pintype "passive"))
      (node (ref "Q8") (pin "2") (pinfunction "E_2") (pintype "passive"))
      (node (ref "Q9") (pin "2") (pinfunction "E_2") (pintype "passive"))
      (node (ref "R11") (pin "2") (pinfunction "2_2") (pintype "passive"))
      (node (ref "R12") (pin "2") (pinfunction "2_2") (pintype "passive"))
      (node (ref "R3") (pin "2") (pinfunction "2_2") (pintype "passive"))
      (node (ref "R5") (pin "1") (pinfunction "1_1") (pintype "passive"))
      (node (ref "RL_CHIP") (pin "20") (pinfunction "20_20") (pintype "passive"))
      (node (ref "RL_CHIP") (pin "30") (pinfunction "30_30") (pintype "passive"))
      (node (ref "RR_CHIP") (pin "20") (pinfunction "20_20") (pintype "passive"))
      (node (ref "RR_CHIP") (pin "28") (pinfunction "28_28") (pintype "passive"))
      (node (ref "RR_CHIP") (pin "29") (pinfunction "29_29") (pintype "passive"))
      (node (ref "S1") (pin "3") (pinfunction "P_3") (pintype "passive"))
      (node (ref "S1") (pin "4") (pinfunction "P1_4") (pintype "passive"))
      (node (ref "X3") (pin "2") (pinfunction "KL_2") (pintype "passive"))
    )
    (net (code "38") (name "LED") (class "Default")
      (node (ref "JP1") (pin "6") (pinfunction "6_6") (pintype "passive"))
      (node (ref "LED1") (pin "C") (pinfunction "C_C") (pintype "passive"))
    )
    (net (code "39") (name "MAIN_LED1") (class "Default")
      (node (ref "MAIN_CHIP") (pin "7") (pinfunction "7_7") (pintype "passive"))
      (node (ref "R18") (pin "1") (pinfunction "1_1") (pintype "passive"))
    )
    (net (code "40") (name "MAIN_LED2") (class "Default")
      (node (ref "MAIN_CHIP") (pin "8") (pinfunction "8_8") (pintype "passive"))
      (node (ref "R19") (pin "1") (pinfunction "1_1") (pintype "passive"))
    )
    (net (code "41") (name "MAIN_LED3") (class "Default")
      (node (ref "MAIN_CHIP") (pin "9") (pinfunction "9_9") (pintype "passive"))
      (node (ref "R20") (pin "1") (pinfunction "1_1") (pintype "passive"))
    )
    (net (code "42") (name "Net-(FL_CHIP-Pad28)") (class "Default")
      (node (ref "FL_CHIP") (pin "28") (pinfunction "28_28") (pintype "passive"))
      (node (ref "R6") (pin "1") (pinfunction "1_1") (pintype "passive"))
    )
    (net (code "43") (name "Net-(FR_CHIP-Pad29)") (class "Default")
      (node (ref "FR_CHIP") (pin "29") (pinfunction "29_29") (pintype "passive"))
      (node (ref "R7") (pin "1") (pinfunction "1_1") (pintype "passive"))
    )
    (net (code "44") (name "Net-(LED1-PadA)") (class "Default")
      (node (ref "LED1") (pin "A") (pinfunction "A_A") (pintype "passive"))
      (node (ref "R5") (pin "2") (pinfunction "2_2") (pintype "passive"))
    )
    (net (code "45") (name "Net-(LED2-PadC)") (class "Default")
      (node (ref "LED2") (pin "C") (pinfunction "C_C") (pintype "passive"))
      (node (ref "R12") (pin "1") (pinfunction "1_1") (pintype "passive"))
    )
    (net (code "46") (name "Net-(LED3-PadC)") (class "Default")
      (node (ref "LED3") (pin "C") (pinfunction "C_C") (pintype "passive"))
      (node (ref "R11") (pin "1") (pinfunction "1_1") (pintype "passive"))
    )
    (net (code "47") (name "Net-(LED4-PadA)") (class "Default")
      (node (ref "LED4") (pin "A") (pinfunction "A_A") (pintype "passive"))
      (node (ref "R34") (pin "1") (pinfunction "1_1") (pintype "passive"))
    )
    (net (code "48") (name "Net-(LED5-PadA)") (class "Default")
      (node (ref "LED5") (pin "A") (pinfunction "A_A") (pintype "passive"))
      (node (ref "R25") (pin "1") (pinfunction "1_1") (pintype "passive"))
    )
    (net (code "49") (name "Net-(LED6-PadA)") (class "Default")
      (node (ref "LED6") (pin "A") (pinfunction "A_A") (pintype "passive"))
      (node (ref "R26") (pin "1") (pinfunction "1_1") (pintype "passive"))
    )
    (net (code "50") (name "Net-(LED7-PadA)") (class "Default")
      (node (ref "LED7") (pin "A") (pinfunction "A_A") (pintype "passive"))
      (node (ref "R35") (pin "1") (pinfunction "1_1") (pintype "passive"))
    )
    (net (code "51") (name "Net-(LED8-PadA)") (class "Default")
      (node (ref "LED8") (pin "A") (pinfunction "A_A") (pintype "passive"))
      (node (ref "R27") (pin "1") (pinfunction "1_1") (pintype "passive"))
    )
    (net (code "52") (name "Net-(LED9-PadA)") (class "Default")
      (node (ref "LED9") (pin "A") (pinfunction "A_A") (pintype "passive"))
      (node (ref "R28") (pin "1") (pinfunction "1_1") (pintype "passive"))
    )
    (net (code "53") (name "Net-(LED10-PadA)") (class "Default")
      (node (ref "LED10") (pin "A") (pinfunction "A_A") (pintype "passive"))
      (node (ref "R29") (pin "1") (pinfunction "1_1") (pintype "passive"))
    )
    (net (code "54") (name "Net-(LED11-PadA)") (class "Default")
      (node (ref "LED11") (pin "A") (pinfunction "A_A") (pintype "passive"))
      (node (ref "R31") (pin "1") (pinfunction "1_1") (pintype "passive"))
    )
    (net (code "55") (name "Net-(LED12-PadA)") (class "Default")
      (node (ref "LED12") (pin "A") (pinfunction "A_A") (pintype "passive"))
      (node (ref "R30") (pin "1") (pinfunction "1_1") (pintype "passive"))
    )
    (net (code "56") (name "Net-(LED13-PadA)") (class "Default")
      (node (ref "LED13") (pin "A") (pinfunction "A_A") (pintype "passive"))
      (node (ref "R33") (pin "1") (pinfunction "1_1") (pintype "passive"))
    )
    (net (code "57") (name "Net-(LED14-PadA)") (class "Default")
      (node (ref "LED14") (pin "A") (pinfunction "A_A") (pintype "passive"))
      (node (ref "R32") (pin "1") (pinfunction "1_1") (pintype "passive"))
    )
    (net (code "58") (name "Net-(Q1-B)") (class "Default")
      (node (ref "Q1") (pin "1") (pinfunction "B_1") (pintype "passive"))
      (node (ref "R24") (pin "2") (pinfunction "2_2") (pintype "passive"))
    )
    (net (code "59") (name "Net-(Q1-C)") (class "Default")
      (node (ref "LED4") (pin "C") (pinfunction "C_C") (pintype "passive"))
      (node (ref "Q1") (pin "3") (pinfunction "C_3") (pintype "passive"))
    )
    (net (code "60") (name "Net-(Q2-B)") (class "Default")
      (node (ref "Q2") (pin "1") (pinfunction "B_1") (pintype "passive"))
      (node (ref "R23") (pin "2") (pinfunction "2_2") (pintype "passive"))
    )
    (net (code "61") (name "Net-(Q2-C)") (class "Default")
      (node (ref "LED7") (pin "C") (pinfunction "C_C") (pintype "passive"))
      (node (ref "Q2") (pin "3") (pinfunction "C_3") (pintype "passive"))
    )
    (net (code "62") (name "Net-(Q3-B)") (class "Default")
      (node (ref "Q3") (pin "1") (pinfunction "B_1") (pintype "passive"))
      (node (ref "R21") (pin "2") (pinfunction "2_2") (pintype "passive"))
    )
    (net (code "63") (name "Net-(Q3-C)") (class "Default")
      (node (ref "LED13") (pin "C") (pinfunction "C_C") (pintype "passive"))
      (node (ref "Q3") (pin "3") (pinfunction "C_3") (pintype "passive"))
    )
    (net (code "64") (name "Net-(Q4-B)") (class "Default")
      (node (ref "Q4") (pin "1") (pinfunction "B_1") (pintype "passive"))
      (node (ref "R22") (pin "2") (pinfunction "2_2") (pintype "passive"))
    )
    (net (code "65") (name "Net-(Q4-C)") (class "Default")
      (node (ref "LED14") (pin "C") (pinfunction "C_C") (pintype "passive"))
      (node (ref "Q4") (pin "3") (pinfunction "C_3") (pintype "passive"))
    )
    (net (code "66") (name "Net-(Q5-B)") (class "Default")
      (node (ref "Q5") (pin "1") (pinfunction "B_1") (pintype "passive"))
      (node (ref "R14") (pin "2") (pinfunction "2_2") (pintype "passive"))
    )
    (net (code "67") (name "Net-(Q5-C)") (class "Default")
      (node (ref "LED5") (pin "C") (pinfunction "C_C") (pintype "passive"))
      (node (ref "Q5") (pin "3") (pinfunction "C_3") (pintype "passive"))
    )
    (net (code "68") (name "Net-(Q6-B)") (class "Default")
      (node (ref "Q6") (pin "1") (pinfunction "B_1") (pintype "passive"))
      (node (ref "R15") (pin "2") (pinfunction "2_2") (pintype "passive"))
    )
    (net (code "69") (name "Net-(Q6-C)") (class "Default")
      (node (ref "LED6") (pin "C") (pinfunction "C_C") (pintype "passive"))
      (node (ref "Q6") (pin "3") (pinfunction "C_3") (pintype "passive"))
    )
    (net (code "70") (name "Net-(Q7-B)") (class "Default")
      (node (ref "Q7") (pin "1") (pinfunction "B_1") (pintype "passive"))
      (node (ref "R17") (pin "2") (pinfunction "2_2") (pintype "passive"))
    )
    (net (code "71") (name "Net-(Q7-C)") (class "Default")
      (node (ref "LED11") (pin "C") (pinfunction "C_C") (pintype "passive"))
      (node (ref "Q7") (pin "3") (pinfunction "C_3") (pintype "passive"))
    )
    (net (code "72") (name "Net-(Q8-B)") (class "Default")
      (node (ref "Q8") (pin "1") (pinfunction "B_1") (pintype "passive"))
      (node (ref "R16") (pin "2") (pinfunction "2_2") (pintype "passive"))
    )
    (net (code "73") (name "Net-(Q8-C)") (class "Default")
      (node (ref "LED12") (pin "C") (pinfunction "C_C") (pintype "passive"))
      (node (ref "Q8") (pin "3") (pinfunction "C_3") (pintype "passive"))
    )
    (net (code "74") (name "Net-(Q9-B)") (class "Default")
      (node (ref "Q9") (pin "1") (pinfunction "B_1") (pintype "passive"))
      (node (ref "R18") (pin "2") (pinfunction "2_2") (pintype "passive"))
    )
    (net (code "75") (name "Net-(Q9-C)") (class "Default")
      (node (ref "LED8") (pin "C") (pinfunction "C_C") (pintype "passive"))
      (node (ref "Q9") (pin "3") (pinfunction "C_3") (pintype "passive"))
    )
    (net (code "76") (name "Net-(Q10-B)") (class "Default")
      (node (ref "Q10") (pin "1") (pinfunction "B_1") (pintype "passive"))
      (node (ref "R19") (pin "2") (pinfunction "2_2") (pintype "passive"))
    )
    (net (code "77") (name "Net-(Q10-C)") (class "Default")
      (node (ref "LED9") (pin "C") (pinfunction "C_C") (pintype "passive"))
      (node (ref "Q10") (pin "3") (pinfunction "C_3") (pintype "passive"))
    )
    (net (code "78") (name "Net-(Q11-B)") (class "Default")
      (node (ref "Q11") (pin "1") (pinfunction "B_1") (pintype "passive"))
      (node (ref "R20") (pin "2") (pinfunction "2_2") (pintype "passive"))
    )
    (net (code "79") (name "Net-(Q11-C)") (class "Default")
      (node (ref "LED10") (pin "C") (pinfunction "C_C") (pintype "passive"))
      (node (ref "Q11") (pin "3") (pinfunction "C_3") (pintype "passive"))
    )
    (net (code "80") (name "Net-(R8-Pad1)") (class "Default")
      (node (ref "R8") (pin "1") (pinfunction "1_1") (pintype "passive"))
      (node (ref "RL_CHIP") (pin "29") (pinfunction "29_29") (pintype "passive"))
    )
    (net (code "81") (name "Net-(R9-Pad1)") (class "Default")
      (node (ref "R9") (pin "1") (pinfunction "1_1") (pintype "passive"))
      (node (ref "RL_CHIP") (pin "28") (pinfunction "28_28") (pintype "passive"))
    )
    (net (code "82") (name "Net-(R10-Pad1)") (class "Default")
      (node (ref "R10") (pin "1") (pinfunction "1_1") (pintype "passive"))
      (node (ref "RR_CHIP") (pin "30") (pinfunction "30_30") (pintype "passive"))
    )
    (net (code "83") (name "RESET") (class "Default")
      (node (ref "C3") (pin "1") (pinfunction "1_1") (pintype "passive"))
      (node (ref "FL_CHIP") (pin "3") (pinfunction "3_3") (pintype "passive"))
      (node (ref "FR_CHIP") (pin "3") (pinfunction "3_3") (pintype "passive"))
      (node (ref "MAIN_CHIP") (pin "3") (pinfunction "3_3") (pintype "passive"))
      (node (ref "RL_CHIP") (pin "3") (pinfunction "3_3") (pintype "passive"))
      (node (ref "RR_CHIP") (pin "3") (pinfunction "3_3") (pintype "passive"))
      (node (ref "S1") (pin "1") (pinfunction "S_1") (pintype "passive"))
      (node (ref "S1") (pin "2") (pinfunction "S1_2") (pintype "passive"))
    )
    (net (code "84") (name "RL_AI0") (class "Default")
      (node (ref "CONNECTOR_REAR1") (pin "37") (pinfunction "37_37") (pintype "passive"))
      (node (ref "RL_CHIP") (pin "26") (pinfunction "26_26") (pintype "passive"))
    )
    (net (code "85") (name "RL_AI1") (class "Default")
      (node (ref "CONNECTOR_REAR1") (pin "38") (pinfunction "38_38") (pintype "passive"))
      (node (ref "RL_CHIP") (pin "25") (pinfunction "25_25") (pintype "passive"))
    )
    (net (code "86") (name "RL_AI2") (class "Default")
      (node (ref "CONNECTOR_REAR1") (pin "39") (pinfunction "39_39") (pintype "passive"))
      (node (ref "RL_CHIP") (pin "24") (pinfunction "24_24") (pintype "passive"))
    )
    (net (code "87") (name "RL_AI3") (class "Default")
      (node (ref "CONNECTOR_REAR1") (pin "36") (pinfunction "36_36") (pintype "passive"))
      (node (ref "RL_CHIP") (pin "23") (pinfunction "23_23") (pintype "passive"))
    )
    (net (code "88") (name "RL_DI0") (class "Default")
      (node (ref "CONNECTOR_REAR1") (pin "12") (pinfunction "12_12") (pintype "passive"))
      (node (ref "RL_CHIP") (pin "13") (pinfunction "13_13") (pintype "passive"))
    )
    (net (code "89") (name "RL_DI1") (class "Default")
      (node (ref "CONNECTOR_REAR1") (pin "14") (pinfunction "14_14") (pintype "passive"))
      (node (ref "RL_CHIP") (pin "14") (pinfunction "14_14") (pintype "passive"))
    )
    (net (code "90") (name "RL_DO0") (class "Default")
      (node (ref "CONNECTOR_REAR1") (pin "3") (pinfunction "3_3") (pintype "passive"))
      (node (ref "RL_CHIP") (pin "38") (pinfunction "38_38") (pintype "passive"))
    )
    (net (code "91") (name "RL_DO1") (class "Default")
      (node (ref "CONNECTOR_REAR1") (pin "4") (pinfunction "4_4") (pintype "passive"))
      (node (ref "RL_CHIP") (pin "37") (pinfunction "37_37") (pintype "passive"))
    )
    (net (code "92") (name "RL_DO2") (class "Default")
      (node (ref "CONNECTOR_REAR1") (pin "5") (pinfunction "5_5") (pintype "passive"))
      (node (ref "RL_CHIP") (pin "36") (pinfunction "36_36") (pintype "passive"))
    )
    (net (code "93") (name "RL_LED1") (class "Default")
      (node (ref "R21") (pin "1") (pinfunction "1_1") (pintype "passive"))
      (node (ref "RL_CHIP") (pin "33") (pinfunction "33_33") (pintype "passive"))
    )
    (net (code "94") (name "RL_LED2") (class "Default")
      (node (ref "R22") (pin "1") (pinfunction "1_1") (pintype "passive"))
      (node (ref "RL_CHIP") (pin "32") (pinfunction "32_32") (pintype "passive"))
    )
    (net (code "95") (name "RL_PWM0") (class "Default")
      (node (ref "CONNECTOR_REAR1") (pin "15") (pinfunction "15_15") (pintype "passive"))
      (node (ref "RL_CHIP") (pin "7") (pinfunction "7_7") (pintype "passive"))
    )
    (net (code "96") (name "RL_PWM1") (class "Default")
      (node (ref "CONNECTOR_REAR1") (pin "16") (pinfunction "16_16") (pintype "passive"))
      (node (ref "RL_CHIP") (pin "8") (pinfunction "8_8") (pintype "passive"))
    )
    (net (code "97") (name "RL_PWM2") (class "Default")
      (node (ref "CONNECTOR_REAR1") (pin "17") (pinfunction "17_17") (pintype "passive"))
      (node (ref "RL_CHIP") (pin "9") (pinfunction "9_9") (pintype "passive"))
    )
    (net (code "98") (name "RL_PWM3") (class "Default")
      (node (ref "CONNECTOR_REAR1") (pin "18") (pinfunction "18_18") (pintype "passive"))
      (node (ref "RL_CHIP") (pin "10") (pinfunction "10_10") (pintype "passive"))
    )
    (net (code "99") (name "RL_PWM4") (class "Default")
      (node (ref "CONNECTOR_REAR1") (pin "19") (pinfunction "19_19") (pintype "passive"))
      (node (ref "RL_CHIP") (pin "11") (pinfunction "11_11") (pintype "passive"))
    )
    (net (code "100") (name "RL_PWM5") (class "Default")
      (node (ref "CONNECTOR_REAR1") (pin "20") (pinfunction "20_20") (pintype "passive"))
      (node (ref "RL_CHIP") (pin "12") (pinfunction "12_12") (pintype "passive"))
    )
    (net (code "101") (name "RR_AI0") (class "Default")
      (node (ref "CONNECTOR_REAR1") (pin "33") (pinfunction "33_33") (pintype "passive"))
      (node (ref "RR_CHIP") (pin "26") (pinfunction "26_26") (pintype "passive"))
    )
    (net (code "102") (name "RR_AI1") (class "Default")
      (node (ref "CONNECTOR_REAR1") (pin "34") (pinfunction "34_34") (pintype "passive"))
      (node (ref "RR_CHIP") (pin "25") (pinfunction "25_25") (pintype "passive"))
    )
    (net (code "103") (name "RR_AI2") (class "Default")
      (node (ref "CONNECTOR_REAR1") (pin "35") (pinfunction "35_35") (pintype "passive"))
      (node (ref "RR_CHIP") (pin "24") (pinfunction "24_24") (pintype "passive"))
    )
    (net (code "104") (name "RR_AI3") (class "Default")
      (node (ref "CONNECTOR_REAR1") (pin "40") (pinfunction "40_40") (pintype "passive"))
      (node (ref "RR_CHIP") (pin "23") (pinfunction "23_23") (pintype "passive"))
    )
    (net (code "105") (name "RR_DI0") (class "Default")
      (node (ref "CONNECTOR_REAR1") (pin "11") (pinfunction "11_11") (pintype "passive"))
      (node (ref "RR_CHIP") (pin "13") (pinfunction "13_13") (pintype "passive"))
    )
    (net (code "106") (name "RR_DI1") (class "Default")
      (node (ref "CONNECTOR_REAR1") (pin "13") (pinfunction "13_13") (pintype "passive"))
      (node (ref "RR_CHIP") (pin "14") (pinfunction "14_14") (pintype "passive"))
    )
    (net (code "107") (name "RR_DO0") (class "Default")
      (node (ref "CONNECTOR_REAR1") (pin "6") (pinfunction "6_6") (pintype "passive"))
      (node (ref "RR_CHIP") (pin "38") (pinfunction "38_38") (pintype "passive"))
    )
    (net (code "108") (name "RR_DO1") (class "Default")
      (node (ref "CONNECTOR_REAR1") (pin "7") (pinfunction "7_7") (pintype "passive"))
      (node (ref "RR_CHIP") (pin "37") (pinfunction "37_37") (pintype "passive"))
    )
    (net (code "109") (name "RR_DO2") (class "Default")
      (node (ref "CONNECTOR_REAR1") (pin "8") (pinfunction "8_8") (pintype "passive"))
      (node (ref "RR_CHIP") (pin "36") (pinfunction "36_36") (pintype "passive"))
    )
    (net (code "110") (name "RR_LED1") (class "Default")
      (node (ref "R17") (pin "1") (pinfunction "1_1") (pintype "passive"))
      (node (ref "RR_CHIP") (pin "33") (pinfunction "33_33") (pintype "passive"))
    )
    (net (code "111") (name "RR_LED2") (class "Default")
      (node (ref "R16") (pin "1") (pinfunction "1_1") (pintype "passive"))
      (node (ref "RR_CHIP") (pin "32") (pinfunction "32_32") (pintype "passive"))
    )
    (net (code "112") (name "RR_PWM0") (class "Default")
      (node (ref "CONNECTOR_REAR1") (pin "21") (pinfunction "21_21") (pintype "passive"))
      (node (ref "RR_CHIP") (pin "7") (pinfunction "7_7") (pintype "passive"))
    )
    (net (code "113") (name "RR_PWM1") (class "Default")
      (node (ref "CONNECTOR_REAR1") (pin "22") (pinfunction "22_22") (pintype "passive"))
      (node (ref "RR_CHIP") (pin "8") (pinfunction "8_8") (pintype "passive"))
    )
    (net (code "114") (name "RR_PWM2") (class "Default")
      (node (ref "CONNECTOR_REAR1") (pin "23") (pinfunction "23_23") (pintype "passive"))
      (node (ref "RR_CHIP") (pin "9") (pinfunction "9_9") (pintype "passive"))
    )
    (net (code "115") (name "RR_PWM3") (class "Default")
      (node (ref "CONNECTOR_REAR1") (pin "24") (pinfunction "24_24") (pintype "passive"))
      (node (ref "RR_CHIP") (pin "10") (pinfunction "10_10") (pintype "passive"))
    )
    (net (code "116") (name "RR_PWM4") (class "Default")
      (node (ref "CONNECTOR_REAR1") (pin "25") (pinfunction "25_25") (pintype "passive"))
      (node (ref "RR_CHIP") (pin "11") (pinfunction "11_11") (pintype "passive"))
    )
    (net (code "117") (name "RR_PWM5") (class "Default")
      (node (ref "CONNECTOR_REAR1") (pin "26") (pinfunction "26_26") (pintype "passive"))
      (node (ref "RR_CHIP") (pin "12") (pinfunction "12_12") (pintype "passive"))
    )
    (net (code "118") (name "UART_RX") (class "Default")
      (node (ref "MAIN_CHIP") (pin "34") (pinfunction "34_34") (pintype "passive"))
      (node (ref "R1") (pin "1") (pinfunction "1_1") (pintype "passive"))
    )
    (net (code "119") (name "UART_TX") (class "Default")
      (node (ref "MAIN_CHIP") (pin "35") (pinfunction "35_35") (pintype "passive"))
      (node (ref "R4") (pin "1") (pinfunction "1_1") (pintype "passive"))
    )
    (net (code "120") (name "VBAT") (class "Default")
      (node (ref "C1") (pin "+") (pinfunction "+_+") (pintype "passive"))
      (node (ref "C2") (pin "+") (pinfunction "+_+") (pintype "passive"))
      (node (ref "DC1") (pin "1") (pinfunction "VIN_1") (pintype "passive"))
      (node (ref "DC2") (pin "1") (pinfunction "VIN_1") (pintype "passive"))
      (node (ref "X3") (pin "1") (pinfunction "KL_1") (pintype "passive"))
    )
    (net (code "121") (name "VCC") (class "Default")
      (node (ref "DC1") (pin "3") (pinfunction "VOUT_3") (pintype "passive"))
      (node (ref "FL_CHIP") (pin "40") (pinfunction "40_40") (pintype "passive"))
      (node (ref "FR_CHIP") (pin "40") (pinfunction "40_40") (pintype "passive"))
      (node (ref "LED2") (pin "A") (pinfunction "A_A") (pintype "passive"))
      (node (ref "MAIN_CHIP") (pin "40") (pinfunction "40_40") (pintype "passive"))
      (node (ref "R10") (pin "2") (pinfunction "2_2") (pintype "passive"))
      (node (ref "R25") (pin "2") (pinfunction "2_2") (pintype "passive"))
      (node (ref "R26") (pin "2") (pinfunction "2_2") (pintype "passive"))
      (node (ref "R27") (pin "2") (pinfunction "2_2") (pintype "passive"))
      (node (ref "R28") (pin "2") (pinfunction "2_2") (pintype "passive"))
      (node (ref "R29") (pin "2") (pinfunction "2_2") (pintype "passive"))
      (node (ref "R30") (pin "2") (pinfunction "2_2") (pintype "passive"))
      (node (ref "R31") (pin "2") (pinfunction "2_2") (pintype "passive"))
      (node (ref "R32") (pin "2") (pinfunction "2_2") (pintype "passive"))
      (node (ref "R33") (pin "2") (pinfunction "2_2") (pintype "passive"))
      (node (ref "R34") (pin "2") (pinfunction "2_2") (pintype "passive"))
      (node (ref "R35") (pin "2") (pinfunction "2_2") (pintype "passive"))
      (node (ref "R6") (pin "2") (pinfunction "2_2") (pintype "passive"))
      (node (ref "R7") (pin "2") (pinfunction "2_2") (pintype "passive"))
      (node (ref "R8") (pin "2") (pinfunction "2_2") (pintype "passive"))
      (node (ref "R9") (pin "2") (pinfunction "2_2") (pintype "passive"))
      (node (ref "RL_CHIP") (pin "40") (pinfunction "40_40") (pintype "passive"))
      (node (ref "RR_CHIP") (pin "40") (pinfunction "40_40") (pintype "passive"))
    )
    (net (code "122") (name "VCC3V3") (class "Default")
      (node (ref "C6") (pin "1") (pinfunction "1_1") (pintype "passive"))
      (node (ref "C7") (pin "+") (pinfunction "+_+") (pintype "passive"))
      (node (ref "DC2") (pin "3") (pinfunction "VOUT_3") (pintype "passive"))
      (node (ref "JP1") (pin "1") (pinfunction "1_1") (pintype "passive"))
      (node (ref "LED3") (pin "A") (pinfunction "A_A") (pintype "passive"))
      (node (ref "R2") (pin "1") (pinfunction "1_1") (pintype "passive"))
    )
    (net (code "123") (name "XBEERESET") (class "Default")
      (node (ref "JP1") (pin "5") (pinfunction "5_5") (pintype "passive"))
      (node (ref "R2") (pin "2") (pinfunction "2_2") (pintype "passive"))
    )
    (net (code "124") (name "XBEERX") (class "Default")
      (node (ref "JP1") (pin "3") (pinfunction "3_3") (pintype "passive"))
      (node (ref "R3") (pin "1") (pinfunction "1_1") (pintype "passive"))
      (node (ref "R4") (pin "2") (pinfunction "2_2") (pintype "passive"))
    )
    (net (code "125") (name "XBEETX") (class "Default")
      (node (ref "JP1") (pin "2") (pinfunction "2_2") (pintype "passive"))
      (node (ref "R1") (pin "2") (pinfunction "2_2") (pintype "passive"))
    )
    (net (code "126") (name "unconnected-(CONECTOR_FRONT1-Pad1)") (class "Default")
      (node (ref "CONECTOR_FRONT1") (pin "1") (pinfunction "1_1") (pintype "passive"))
    )
    (net (code "127") (name "unconnected-(CONECTOR_FRONT1-Pad2)") (class "Default")
      (node (ref "CONECTOR_FRONT1") (pin "2") (pinfunction "2_2") (pintype "passive"))
    )
    (net (code "128") (name "unconnected-(CONECTOR_FRONT1-Pad9)") (class "Default")
      (node (ref "CONECTOR_FRONT1") (pin "9") (pinfunction "9_9") (pintype "passive"))
    )
    (net (code "129") (name "unconnected-(CONECTOR_FRONT1-Pad29)") (class "Default")
      (node (ref "CONECTOR_FRONT1") (pin "29") (pinfunction "29_29") (pintype "passive"))
    )
    (net (code "130") (name "unconnected-(CONECTOR_FRONT1-Pad30)") (class "Default")
      (node (ref "CONECTOR_FRONT1") (pin "30") (pinfunction "30_30") (pintype "passive"))
    )
    (net (code "131") (name "unconnected-(CONNECTOR_REAR1-Pad1)") (class "Default")
      (node (ref "CONNECTOR_REAR1") (pin "1") (pinfunction "1_1") (pintype "passive"))
    )
    (net (code "132") (name "unconnected-(CONNECTOR_REAR1-Pad2)") (class "Default")
      (node (ref "CONNECTOR_REAR1") (pin "2") (pinfunction "2_2") (pintype "passive"))
    )
    (net (code "133") (name "unconnected-(CONNECTOR_REAR1-Pad9)") (class "Default")
      (node (ref "CONNECTOR_REAR1") (pin "9") (pinfunction "9_9") (pintype "passive"))
    )
    (net (code "134") (name "unconnected-(CONNECTOR_REAR1-Pad29)") (class "Default")
      (node (ref "CONNECTOR_REAR1") (pin "29") (pinfunction "29_29") (pintype "passive"))
    )
    (net (code "135") (name "unconnected-(CONNECTOR_REAR1-Pad30)") (class "Default")
      (node (ref "CONNECTOR_REAR1") (pin "30") (pinfunction "30_30") (pintype "passive"))
    )
    (net (code "136") (name "unconnected-(FL_CHIP-Pad1)") (class "Default")
      (node (ref "FL_CHIP") (pin "1") (pinfunction "1_1") (pintype "passive"))
    )
    (net (code "137") (name "unconnected-(FL_CHIP-Pad2)") (class "Default")
      (node (ref "FL_CHIP") (pin "2") (pinfunction "2_2") (pintype "passive"))
    )
    (net (code "138") (name "unconnected-(FL_CHIP-Pad4)") (class "Default")
      (node (ref "FL_CHIP") (pin "4") (pinfunction "4_4") (pintype "passive"))
    )
    (net (code "139") (name "unconnected-(FL_CHIP-Pad5)") (class "Default")
      (node (ref "FL_CHIP") (pin "5") (pinfunction "5_5") (pintype "passive"))
    )
    (net (code "140") (name "unconnected-(FL_CHIP-Pad6)") (class "Default")
      (node (ref "FL_CHIP") (pin "6") (pinfunction "6_6") (pintype "passive"))
    )
    (net (code "141") (name "unconnected-(FL_CHIP-Pad15)") (class "Default")
      (node (ref "FL_CHIP") (pin "15") (pinfunction "15_15") (pintype "passive"))
    )
    (net (code "142") (name "unconnected-(FL_CHIP-Pad16)") (class "Default")
      (node (ref "FL_CHIP") (pin "16") (pinfunction "16_16") (pintype "passive"))
    )
    (net (code "143") (name "unconnected-(FL_CHIP-Pad17)") (class "Default")
      (node (ref "FL_CHIP") (pin "17") (pinfunction "17_17") (pintype "passive"))
    )
    (net (code "144") (name "unconnected-(FL_CHIP-Pad21)") (class "Default")
      (node (ref "FL_CHIP") (pin "21") (pinfunction "21_21") (pintype "passive"))
    )
    (net (code "145") (name "unconnected-(FL_CHIP-Pad22)") (class "Default")
      (node (ref "FL_CHIP") (pin "22") (pinfunction "22_22") (pintype "passive"))
    )
    (net (code "146") (name "unconnected-(FL_CHIP-Pad27)") (class "Default")
      (node (ref "FL_CHIP") (pin "27") (pinfunction "27_27") (pintype "passive"))
    )
    (net (code "147") (name "unconnected-(FL_CHIP-Pad31)") (class "Default")
      (node (ref "FL_CHIP") (pin "31") (pinfunction "31_31") (pintype "passive"))
    )
    (net (code "148") (name "unconnected-(FL_CHIP-Pad34)") (class "Default")
      (node (ref "FL_CHIP") (pin "34") (pinfunction "34_34") (pintype "passive"))
    )
    (net (code "149") (name "unconnected-(FL_CHIP-Pad35)") (class "Default")
      (node (ref "FL_CHIP") (pin "35") (pinfunction "35_35") (pintype "passive"))
    )
    (net (code "150") (name "unconnected-(FL_CHIP-Pad39)") (class "Default")
      (node (ref "FL_CHIP") (pin "39") (pinfunction "39_39") (pintype "passive"))
    )
    (net (code "151") (name "unconnected-(FR_CHIP-Pad1)") (class "Default")
      (node (ref "FR_CHIP") (pin "1") (pinfunction "1_1") (pintype "passive"))
    )
    (net (code "152") (name "unconnected-(FR_CHIP-Pad2)") (class "Default")
      (node (ref "FR_CHIP") (pin "2") (pinfunction "2_2") (pintype "passive"))
    )
    (net (code "153") (name "unconnected-(FR_CHIP-Pad4)") (class "Default")
      (node (ref "FR_CHIP") (pin "4") (pinfunction "4_4") (pintype "passive"))
    )
    (net (code "154") (name "unconnected-(FR_CHIP-Pad5)") (class "Default")
      (node (ref "FR_CHIP") (pin "5") (pinfunction "5_5") (pintype "passive"))
    )
    (net (code "155") (name "unconnected-(FR_CHIP-Pad6)") (class "Default")
      (node (ref "FR_CHIP") (pin "6") (pinfunction "6_6") (pintype "passive"))
    )
    (net (code "156") (name "unconnected-(FR_CHIP-Pad15)") (class "Default")
      (node (ref "FR_CHIP") (pin "15") (pinfunction "15_15") (pintype "passive"))
    )
    (net (code "157") (name "unconnected-(FR_CHIP-Pad16)") (class "Default")
      (node (ref "FR_CHIP") (pin "16") (pinfunction "16_16") (pintype "passive"))
    )
    (net (code "158") (name "unconnected-(FR_CHIP-Pad17)") (class "Default")
      (node (ref "FR_CHIP") (pin "17") (pinfunction "17_17") (pintype "passive"))
    )
    (net (code "159") (name "unconnected-(FR_CHIP-Pad21)") (class "Default")
      (node (ref "FR_CHIP") (pin "21") (pinfunction "21_21") (pintype "passive"))
    )
    (net (code "160") (name "unconnected-(FR_CHIP-Pad22)") (class "Default")
      (node (ref "FR_CHIP") (pin "22") (pinfunction "22_22") (pintype "passive"))
    )
    (net (code "161") (name "unconnected-(FR_CHIP-Pad27)") (class "Default")
      (node (ref "FR_CHIP") (pin "27") (pinfunction "27_27") (pintype "passive"))
    )
    (net (code "162") (name "unconnected-(FR_CHIP-Pad31)") (class "Default")
      (node (ref "FR_CHIP") (pin "31") (pinfunction "31_31") (pintype "passive"))
    )
    (net (code "163") (name "unconnected-(FR_CHIP-Pad34)") (class "Default")
      (node (ref "FR_CHIP") (pin "34") (pinfunction "34_34") (pintype "passive"))
    )
    (net (code "164") (name "unconnected-(FR_CHIP-Pad35)") (class "Default")
      (node (ref "FR_CHIP") (pin "35") (pinfunction "35_35") (pintype "passive"))
    )
    (net (code "165") (name "unconnected-(FR_CHIP-Pad39)") (class "Default")
      (node (ref "FR_CHIP") (pin "39") (pinfunction "39_39") (pintype "passive"))
    )
    (net (code "166") (name "unconnected-(JP1-Pad4)") (class "Default")
      (node (ref "JP1") (pin "4") (pinfunction "4_4") (pintype "passive"))
    )
    (net (code "167") (name "unconnected-(JP1-Pad7)") (class "Default")
      (node (ref "JP1") (pin "7") (pinfunction "7_7") (pintype "passive"))
    )
    (net (code "168") (name "unconnected-(JP1-Pad8)") (class "Default")
      (node (ref "JP1") (pin "8") (pinfunction "8_8") (pintype "passive"))
    )
    (net (code "169") (name "unconnected-(JP1-Pad9)") (class "Default")
      (node (ref "JP1") (pin "9") (pinfunction "9_9") (pintype "passive"))
    )
    (net (code "170") (name "unconnected-(JP2-Pad1)") (class "Default")
      (node (ref "JP2") (pin "1") (pinfunction "1_1") (pintype "passive"))
    )
    (net (code "171") (name "unconnected-(JP2-Pad2)") (class "Default")
      (node (ref "JP2") (pin "2") (pinfunction "2_2") (pintype "passive"))
    )
    (net (code "172") (name "unconnected-(JP2-Pad3)") (class "Default")
      (node (ref "JP2") (pin "3") (pinfunction "3_3") (pintype "passive"))
    )
    (net (code "173") (name "unconnected-(JP2-Pad4)") (class "Default")
      (node (ref "JP2") (pin "4") (pinfunction "4_4") (pintype "passive"))
    )
    (net (code "174") (name "unconnected-(JP2-Pad5)") (class "Default")
      (node (ref "JP2") (pin "5") (pinfunction "5_5") (pintype "passive"))
    )
    (net (code "175") (name "unconnected-(JP2-Pad6)") (class "Default")
      (node (ref "JP2") (pin "6") (pinfunction "6_6") (pintype "passive"))
    )
    (net (code "176") (name "unconnected-(JP2-Pad7)") (class "Default")
      (node (ref "JP2") (pin "7") (pinfunction "7_7") (pintype "passive"))
    )
    (net (code "177") (name "unconnected-(JP2-Pad8)") (class "Default")
      (node (ref "JP2") (pin "8") (pinfunction "8_8") (pintype "passive"))
    )
    (net (code "178") (name "unconnected-(JP2-Pad9)") (class "Default")
      (node (ref "JP2") (pin "9") (pinfunction "9_9") (pintype "passive"))
    )
    (net (code "179") (name "unconnected-(JP2-Pad10)") (class "Default")
      (node (ref "JP2") (pin "10") (pinfunction "10_10") (pintype "passive"))
    )
    (net (code "180") (name "unconnected-(MAIN_CHIP-Pad1)") (class "Default")
      (node (ref "MAIN_CHIP") (pin "1") (pinfunction "1_1") (pintype "passive"))
    )
    (net (code "181") (name "unconnected-(MAIN_CHIP-Pad2)") (class "Default")
      (node (ref "MAIN_CHIP") (pin "2") (pinfunction "2_2") (pintype "passive"))
    )
    (net (code "182") (name "unconnected-(MAIN_CHIP-Pad4)") (class "Default")
      (node (ref "MAIN_CHIP") (pin "4") (pinfunction "4_4") (pintype "passive"))
    )
    (net (code "183") (name "unconnected-(MAIN_CHIP-Pad5)") (class "Default")
      (node (ref "MAIN_CHIP") (pin "5") (pinfunction "5_5") (pintype "passive"))
    )
    (net (code "184") (name "unconnected-(MAIN_CHIP-Pad6)") (class "Default")
      (node (ref "MAIN_CHIP") (pin "6") (pinfunction "6_6") (pintype "passive"))
    )
    (net (code "185") (name "unconnected-(MAIN_CHIP-Pad10)") (class "Default")
      (node (ref "MAIN_CHIP") (pin "10") (pinfunction "10_10") (pintype "passive"))
    )
    (net (code "186") (name "unconnected-(MAIN_CHIP-Pad11)") (class "Default")
      (node (ref "MAIN_CHIP") (pin "11") (pinfunction "11_11") (pintype "passive"))
    )
    (net (code "187") (name "unconnected-(MAIN_CHIP-Pad12)") (class "Default")
      (node (ref "MAIN_CHIP") (pin "12") (pinfunction "12_12") (pintype "passive"))
    )
    (net (code "188") (name "unconnected-(MAIN_CHIP-Pad13)") (class "Default")
      (node (ref "MAIN_CHIP") (pin "13") (pinfunction "13_13") (pintype "passive"))
    )
    (net (code "189") (name "unconnected-(MAIN_CHIP-Pad14)") (class "Default")
      (node (ref "MAIN_CHIP") (pin "14") (pinfunction "14_14") (pintype "passive"))
    )
    (net (code "190") (name "unconnected-(MAIN_CHIP-Pad15)") (class "Default")
      (node (ref "MAIN_CHIP") (pin "15") (pinfunction "15_15") (pintype "passive"))
    )
    (net (code "191") (name "unconnected-(MAIN_CHIP-Pad16)") (class "Default")
      (node (ref "MAIN_CHIP") (pin "16") (pinfunction "16_16") (pintype "passive"))
    )
    (net (code "192") (name "unconnected-(MAIN_CHIP-Pad17)") (class "Default")
      (node (ref "MAIN_CHIP") (pin "17") (pinfunction "17_17") (pintype "passive"))
    )
    (net (code "193") (name "unconnected-(MAIN_CHIP-Pad21)") (class "Default")
      (node (ref "MAIN_CHIP") (pin "21") (pinfunction "21_21") (pintype "passive"))
    )
    (net (code "194") (name "unconnected-(MAIN_CHIP-Pad22)") (class "Default")
      (node (ref "MAIN_CHIP") (pin "22") (pinfunction "22_22") (pintype "passive"))
    )
    (net (code "195") (name "unconnected-(MAIN_CHIP-Pad23)") (class "Default")
      (node (ref "MAIN_CHIP") (pin "23") (pinfunction "23_23") (pintype "passive"))
    )
    (net (code "196") (name "unconnected-(MAIN_CHIP-Pad24)") (class "Default")
      (node (ref "MAIN_CHIP") (pin "24") (pinfunction "24_24") (pintype "passive"))
    )
    (net (code "197") (name "unconnected-(MAIN_CHIP-Pad25)") (class "Default")
      (node (ref "MAIN_CHIP") (pin "25") (pinfunction "25_25") (pintype "passive"))
    )
    (net (code "198") (name "unconnected-(MAIN_CHIP-Pad26)") (class "Default")
      (node (ref "MAIN_CHIP") (pin "26") (pinfunction "26_26") (pintype "passive"))
    )
    (net (code "199") (name "unconnected-(MAIN_CHIP-Pad27)") (class "Default")
      (node (ref "MAIN_CHIP") (pin "27") (pinfunction "27_27") (pintype "passive"))
    )
    (net (code "200") (name "unconnected-(MAIN_CHIP-Pad31)") (class "Default")
      (node (ref "MAIN_CHIP") (pin "31") (pinfunction "31_31") (pintype "passive"))
    )
    (net (code "201") (name "unconnected-(MAIN_CHIP-Pad32)") (class "Default")
      (node (ref "MAIN_CHIP") (pin "32") (pinfunction "32_32") (pintype "passive"))
    )
    (net (code "202") (name "unconnected-(MAIN_CHIP-Pad33)") (class "Default")
      (node (ref "MAIN_CHIP") (pin "33") (pinfunction "33_33") (pintype "passive"))
    )
    (net (code "203") (name "unconnected-(MAIN_CHIP-Pad36)") (class "Default")
      (node (ref "MAIN_CHIP") (pin "36") (pinfunction "36_36") (pintype "passive"))
    )
    (net (code "204") (name "unconnected-(MAIN_CHIP-Pad37)") (class "Default")
      (node (ref "MAIN_CHIP") (pin "37") (pinfunction "37_37") (pintype "passive"))
    )
    (net (code "205") (name "unconnected-(MAIN_CHIP-Pad38)") (class "Default")
      (node (ref "MAIN_CHIP") (pin "38") (pinfunction "38_38") (pintype "passive"))
    )
    (net (code "206") (name "unconnected-(MAIN_CHIP-Pad39)") (class "Default")
      (node (ref "MAIN_CHIP") (pin "39") (pinfunction "39_39") (pintype "passive"))
    )
    (net (code "207") (name "unconnected-(RL_CHIP-Pad1)") (class "Default")
      (node (ref "RL_CHIP") (pin "1") (pinfunction "1_1") (pintype "passive"))
    )
    (net (code "208") (name "unconnected-(RL_CHIP-Pad2)") (class "Default")
      (node (ref "RL_CHIP") (pin "2") (pinfunction "2_2") (pintype "passive"))
    )
    (net (code "209") (name "unconnected-(RL_CHIP-Pad4)") (class "Default")
      (node (ref "RL_CHIP") (pin "4") (pinfunction "4_4") (pintype "passive"))
    )
    (net (code "210") (name "unconnected-(RL_CHIP-Pad5)") (class "Default")
      (node (ref "RL_CHIP") (pin "5") (pinfunction "5_5") (pintype "passive"))
    )
    (net (code "211") (name "unconnected-(RL_CHIP-Pad6)") (class "Default")
      (node (ref "RL_CHIP") (pin "6") (pinfunction "6_6") (pintype "passive"))
    )
    (net (code "212") (name "unconnected-(RL_CHIP-Pad15)") (class "Default")
      (node (ref "RL_CHIP") (pin "15") (pinfunction "15_15") (pintype "passive"))
    )
    (net (code "213") (name "unconnected-(RL_CHIP-Pad16)") (class "Default")
      (node (ref "RL_CHIP") (pin "16") (pinfunction "16_16") (pintype "passive"))
    )
    (net (code "214") (name "unconnected-(RL_CHIP-Pad17)") (class "Default")
      (node (ref "RL_CHIP") (pin "17") (pinfunction "17_17") (pintype "passive"))
    )
    (net (code "215") (name "unconnected-(RL_CHIP-Pad21)") (class "Default")
      (node (ref "RL_CHIP") (pin "21") (pinfunction "21_21") (pintype "passive"))
    )
    (net (code "216") (name "unconnected-(RL_CHIP-Pad22)") (class "Default")
      (node (ref "RL_CHIP") (pin "22") (pinfunction "22_22") (pintype "passive"))
    )
    (net (code "217") (name "unconnected-(RL_CHIP-Pad27)") (class "Default")
      (node (ref "RL_CHIP") (pin "27") (pinfunction "27_27") (pintype "passive"))
    )
    (net (code "218") (name "unconnected-(RL_CHIP-Pad31)") (class "Default")
      (node (ref "RL_CHIP") (pin "31") (pinfunction "31_31") (pintype "passive"))
    )
    (net (code "219") (name "unconnected-(RL_CHIP-Pad34)") (class "Default")
      (node (ref "RL_CHIP") (pin "34") (pinfunction "34_34") (pintype "passive"))
    )
    (net (code "220") (name "unconnected-(RL_CHIP-Pad35)") (class "Default")
      (node (ref "RL_CHIP") (pin "35") (pinfunction "35_35") (pintype "passive"))
    )
    (net (code "221") (name "unconnected-(RL_CHIP-Pad39)") (class "Default")
      (node (ref "RL_CHIP") (pin "39") (pinfunction "39_39") (pintype "passive"))
    )
    (net (code "222") (name "unconnected-(RR_CHIP-Pad1)") (class "Default")
      (node (ref "RR_CHIP") (pin "1") (pinfunction "1_1") (pintype "passive"))
    )
    (net (code "223") (name "unconnected-(RR_CHIP-Pad2)") (class "Default")
      (node (ref "RR_CHIP") (pin "2") (pinfunction "2_2") (pintype "passive"))
    )
    (net (code "224") (name "unconnected-(RR_CHIP-Pad4)") (class "Default")
      (node (ref "RR_CHIP") (pin "4") (pinfunction "4_4") (pintype "passive"))
    )
    (net (code "225") (name "unconnected-(RR_CHIP-Pad5)") (class "Default")
      (node (ref "RR_CHIP") (pin "5") (pinfunction "5_5") (pintype "passive"))
    )
    (net (code "226") (name "unconnected-(RR_CHIP-Pad6)") (class "Default")
      (node (ref "RR_CHIP") (pin "6") (pinfunction "6_6") (pintype "passive"))
    )
    (net (code "227") (name "unconnected-(RR_CHIP-Pad15)") (class "Default")
      (node (ref "RR_CHIP") (pin "15") (pinfunction "15_15") (pintype "passive"))
    )
    (net (code "228") (name "unconnected-(RR_CHIP-Pad16)") (class "Default")
      (node (ref "RR_CHIP") (pin "16") (pinfunction "16_16") (pintype "passive"))
    )
    (net (code "229") (name "unconnected-(RR_CHIP-Pad17)") (class "Default")
      (node (ref "RR_CHIP") (pin "17") (pinfunction "17_17") (pintype "passive"))
    )
    (net (code "230") (name "unconnected-(RR_CHIP-Pad21)") (class "Default")
      (node (ref "RR_CHIP") (pin "21") (pinfunction "21_21") (pintype "passive"))
    )
    (net (code "231") (name "unconnected-(RR_CHIP-Pad22)") (class "Default")
      (node (ref "RR_CHIP") (pin "22") (pinfunction "22_22") (pintype "passive"))
    )
    (net (code "232") (name "unconnected-(RR_CHIP-Pad27)") (class "Default")
      (node (ref "RR_CHIP") (pin "27") (pinfunction "27_27") (pintype "passive"))
    )
    (net (code "233") (name "unconnected-(RR_CHIP-Pad31)") (class "Default")
      (node (ref "RR_CHIP") (pin "31") (pinfunction "31_31") (pintype "passive"))
    )
    (net (code "234") (name "unconnected-(RR_CHIP-Pad34)") (class "Default")
      (node (ref "RR_CHIP") (pin "34") (pinfunction "34_34") (pintype "passive"))
    )
    (net (code "235") (name "unconnected-(RR_CHIP-Pad35)") (class "Default")
      (node (ref "RR_CHIP") (pin "35") (pinfunction "35_35") (pintype "passive"))
    )
    (net (code "236") (name "unconnected-(RR_CHIP-Pad39)") (class "Default")
      (node (ref "RR_CHIP") (pin "39") (pinfunction "39_39") (pintype "passive"))
    )
    (net (code "237") (name "unconnected-(X4-Pad1)") (class "Default")
      (node (ref "X4") (pin "1") (pinfunction "1_1") (pintype "passive"))
    )
    (net (code "238") (name "unconnected-(X4-Pad3)") (class "Default")
      (node (ref "X4") (pin "3") (pinfunction "3_3") (pintype "passive"))
    )
    (net (code "239") (name "unconnected-(X4-Pad4)") (class "Default")
      (node (ref "X4") (pin "4") (pinfunction "4_4") (pintype "passive"))
    )
    (net (code "240") (name "unconnected-(X4-Pad5)") (class "Default")
      (node (ref "X4") (pin "5") (pinfunction "5_5") (pintype "passive"))
    )
    (net (code "241") (name "unconnected-(X4-Pad6)") (class "Default")
      (node (ref "X4") (pin "6") (pinfunction "6_6") (pintype "passive"))
    )
    (net (code "242") (name "unconnected-(X4-Pad8)") (class "Default")
      (node (ref "X4") (pin "8") (pinfunction "8_8") (pintype "passive"))
    )
    (net (code "243") (name "unconnected-(X4-Pad9)") (class "Default")
      (node (ref "X4") (pin "9") (pinfunction "9_9") (pintype "passive"))
    )
  )
)
